# lpc1788_board.net
KiCad netlist of a schematic drawn in EAGLE
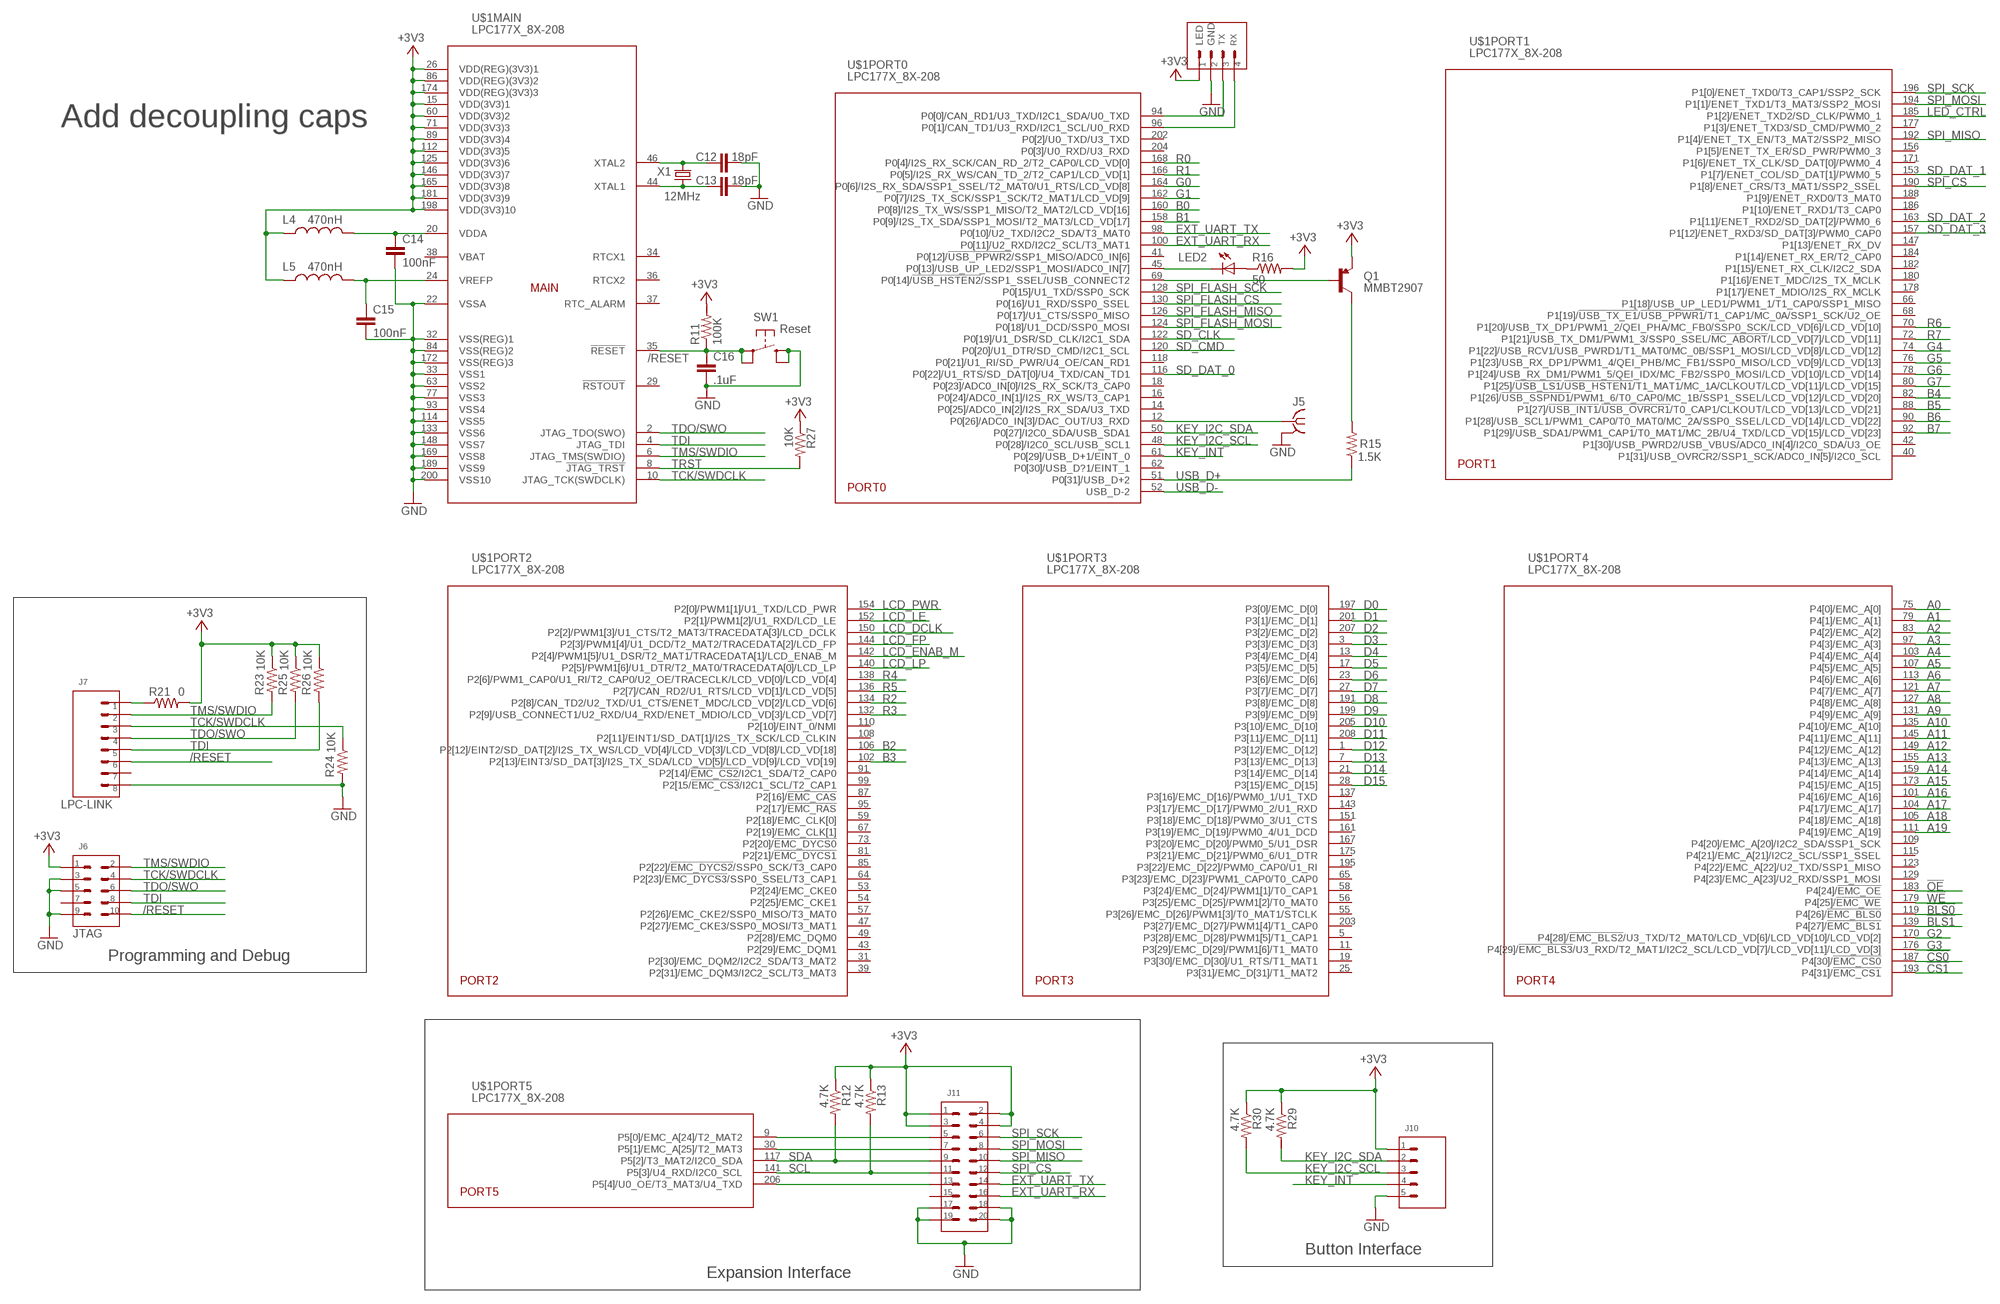
[diagram p0: schematic, sheet 1]
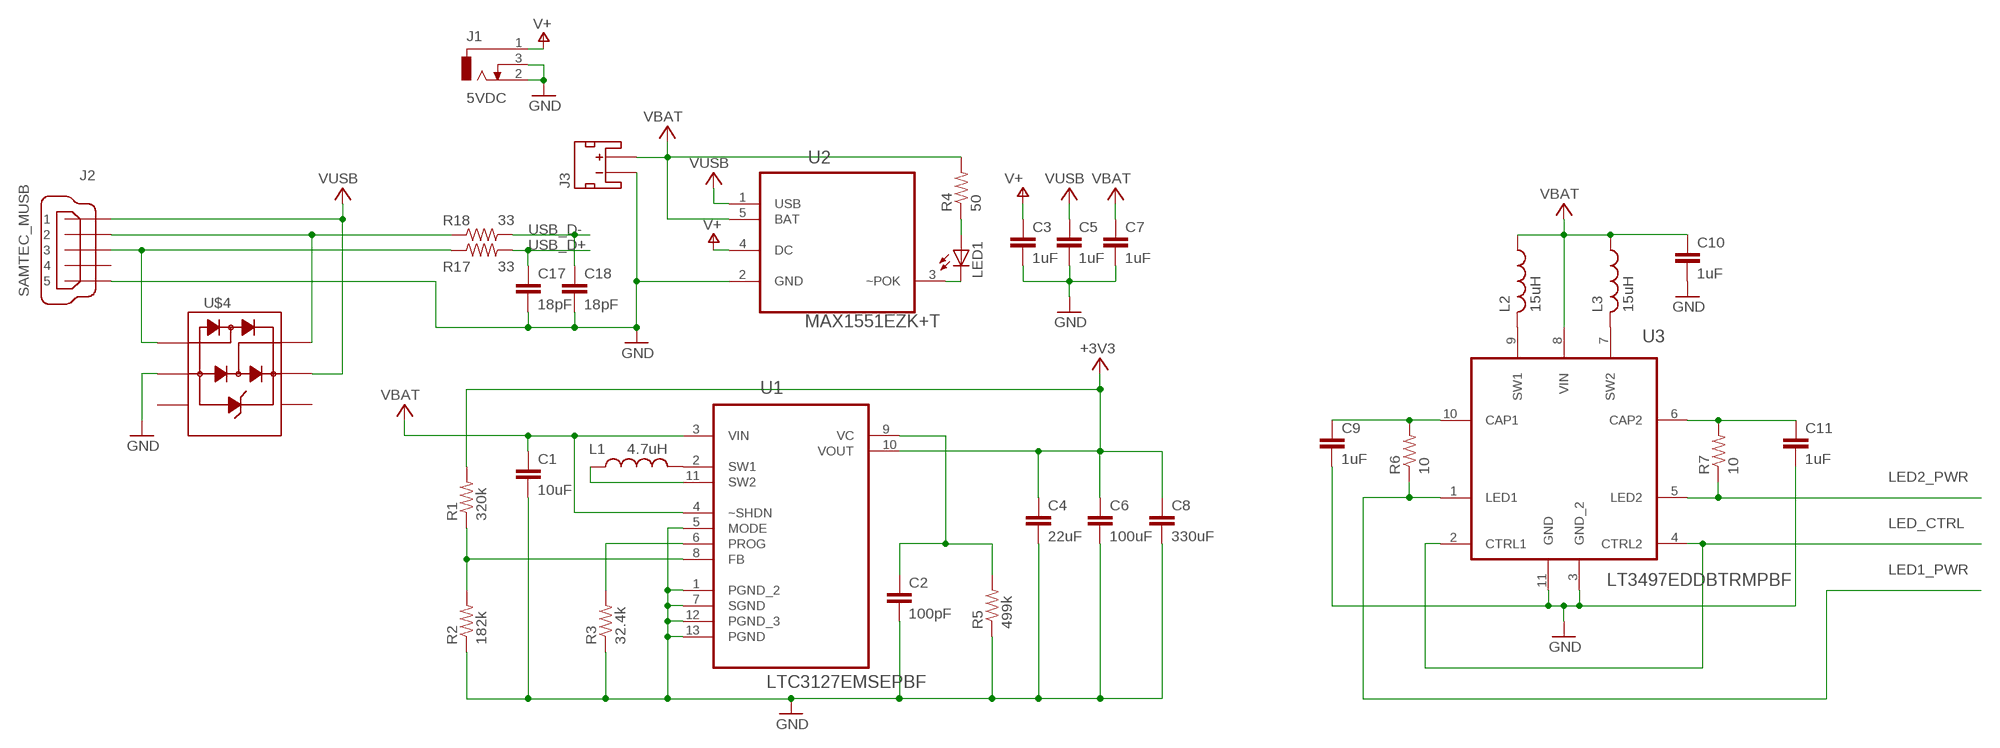
[diagram p1: schematic, sheet 2]
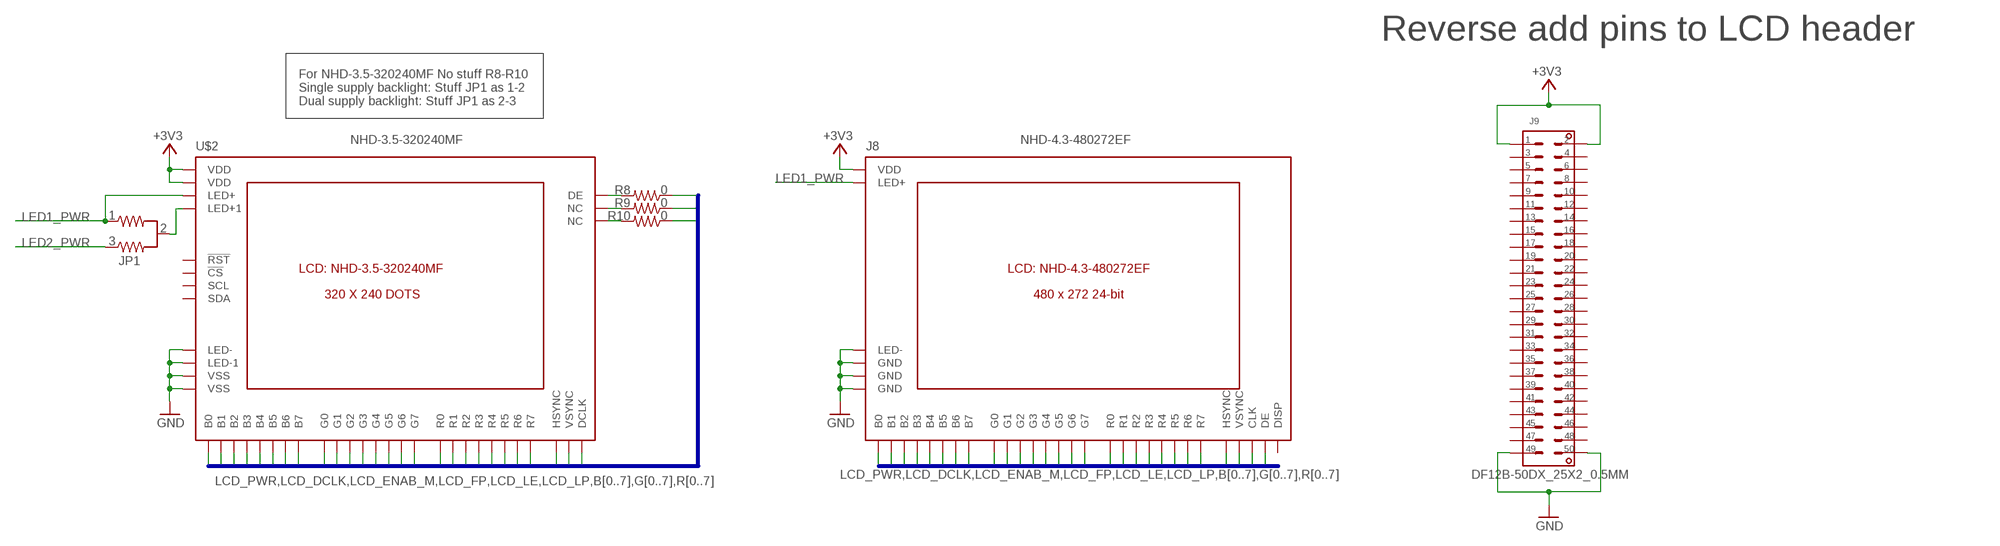
[diagram p2: schematic, sheet 3]
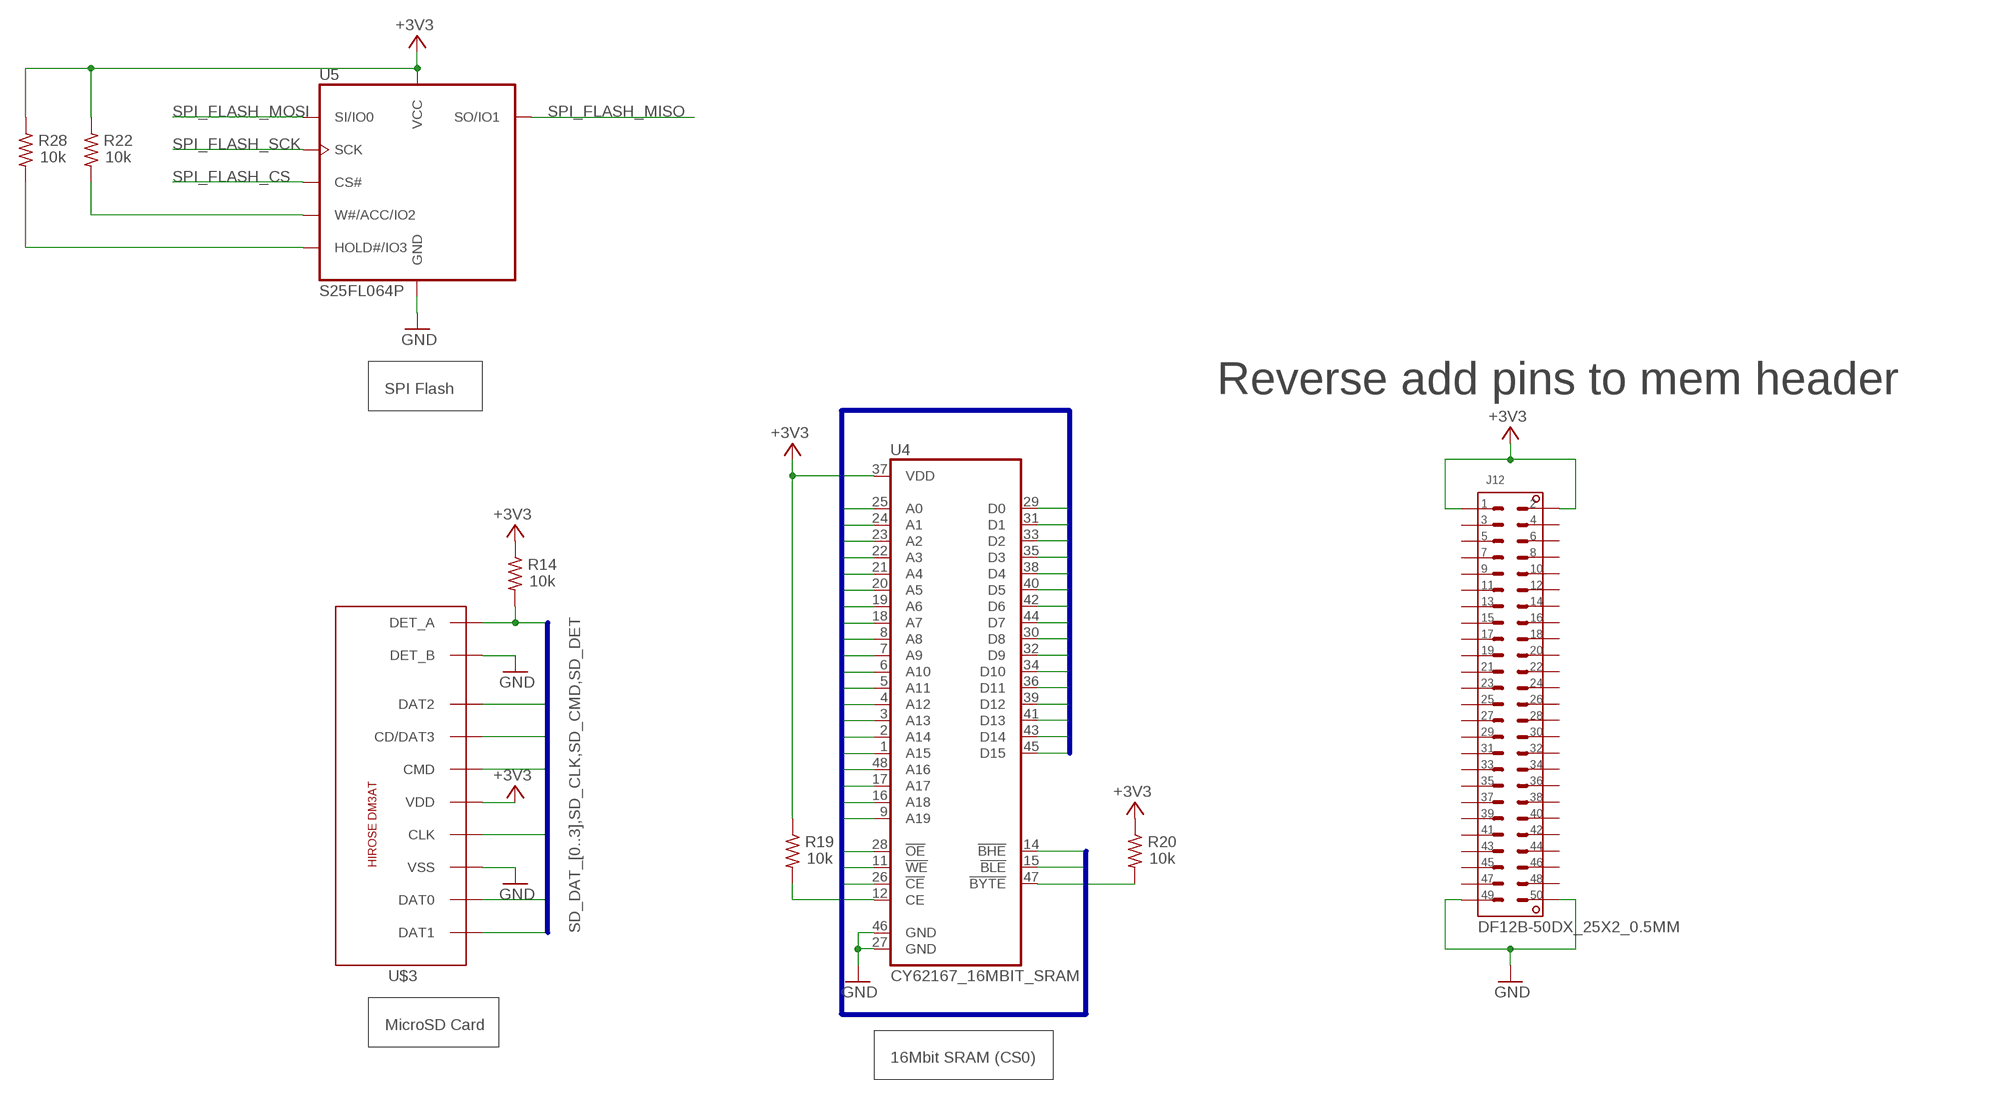
[diagram p3: schematic, sheet 4]

(export (version "E")
  (design (tool "Eeschema 10.0.6"))
  (components
    (comp (ref "C1")
      (value "10uF")
      (footprint "eagle-import:C0402")
      (libsource (lib "eagle-import") (part "C-EUC0402"))
    )
    (comp (ref "C2")
      (value "100pF")
      (footprint "eagle-import:C0402")
      (libsource (lib "eagle-import") (part "C-EUC0402"))
    )
    (comp (ref "C3")
      (value "1uF")
      (footprint "eagle-import:C0402")
      (libsource (lib "eagle-import") (part "C-EUC0402"))
    )
    (comp (ref "C4")
      (value "22uF")
      (footprint "eagle-import:C0805")
      (libsource (lib "eagle-import") (part "C-EUC0805"))
    )
    (comp (ref "C5")
      (value "1uF")
      (footprint "eagle-import:C0402")
      (libsource (lib "eagle-import") (part "C-EUC0402"))
    )
    (comp (ref "C6")
      (value "100uF")
      (footprint "eagle-import:C1206")
      (libsource (lib "eagle-import") (part "C-EUC1206"))
    )
    (comp (ref "C7")
      (value "1uF")
      (footprint "eagle-import:C0402")
      (libsource (lib "eagle-import") (part "C-EUC0402"))
    )
    (comp (ref "C8")
      (value "330uF")
      (footprint "eagle-import:C1206")
      (libsource (lib "eagle-import") (part "C-EUC1206"))
    )
    (comp (ref "C9")
      (value "1uF")
      (footprint "eagle-import:C0805")
      (libsource (lib "eagle-import") (part "C-EUC0805"))
    )
    (comp (ref "C10")
      (value "1uF")
      (footprint "eagle-import:C0402")
      (libsource (lib "eagle-import") (part "C-EUC0402"))
    )
    (comp (ref "C11")
      (value "1uF")
      (footprint "eagle-import:C0805")
      (libsource (lib "eagle-import") (part "C-EUC0805"))
    )
    (comp (ref "C17")
      (value "18pF")
      (footprint "eagle-import:C0402")
      (libsource (lib "eagle-import") (part "C-EUC0402"))
    )
    (comp (ref "C18")
      (value "18pF")
      (footprint "eagle-import:C0402")
      (libsource (lib "eagle-import") (part "C-EUC0402"))
    )
    (comp (ref "J1")
      (value "5VDC")
      (footprint "eagle-import:PJ-045")
      (libsource (lib "eagle-import") (part "DC_POWER_JACK_PJ-045"))
    )
    (comp (ref "J2")
      (value "SAMTEC_MUSB")
      (footprint "eagle-import:MUSB-05-X-B-SM-A")
      (libsource (lib "eagle-import") (part "SAMTEC_MUSB"))
    )
    (comp (ref "J3")
      (value "JST_2MM_SMT")
      (footprint "eagle-import:JST_2MM_SMT")
      (libsource (lib "eagle-import") (part "JST_2MM_SMT"))
    )
    (comp (ref "L1")
      (value "4.7uH")
      (footprint "eagle-import:NR6028")
      (libsource (lib "eagle-import") (part "INDUCTOR_NR6028"))
    )
    (comp (ref "L2")
      (value "15uH")
      (footprint "eagle-import:L3225M")
      (libsource (lib "eagle-import") (part "L-USL3225M"))
    )
    (comp (ref "L3")
      (value "15uH")
      (footprint "eagle-import:L3225M")
      (libsource (lib "eagle-import") (part "L-USL3225M"))
    )
    (comp (ref "LED1")
      (value "CHG")
      (footprint "eagle-import:CHIPLED_0603")
      (libsource (lib "eagle-import") (part "LEDCHIPLED_0603"))
    )
    (comp (ref "R1")
      (value "320k")
      (footprint "eagle-import:R0402")
      (libsource (lib "eagle-import") (part "R-US_R0402"))
    )
    (comp (ref "R2")
      (value "182k")
      (footprint "eagle-import:R0402")
      (libsource (lib "eagle-import") (part "R-US_R0402"))
    )
    (comp (ref "R3")
      (value "32.4k")
      (footprint "eagle-import:R0402")
      (libsource (lib "eagle-import") (part "R-US_R0402"))
    )
    (comp (ref "R4")
      (value "50")
      (footprint "eagle-import:R0402")
      (libsource (lib "eagle-import") (part "R-US_R0402"))
    )
    (comp (ref "R5")
      (value "499k")
      (footprint "eagle-import:R0402")
      (libsource (lib "eagle-import") (part "R-US_R0402"))
    )
    (comp (ref "R6")
      (value "10")
      (footprint "eagle-import:R0402")
      (libsource (lib "eagle-import") (part "R-US_R0402"))
    )
    (comp (ref "R7")
      (value "10")
      (footprint "eagle-import:R0402")
      (libsource (lib "eagle-import") (part "R-US_R0402"))
    )
    (comp (ref "R17")
      (value "33")
      (footprint "eagle-import:R0402")
      (libsource (lib "eagle-import") (part "R-US_R0402"))
    )
    (comp (ref "R18")
      (value "33")
      (footprint "eagle-import:R0402")
      (libsource (lib "eagle-import") (part "R-US_R0402"))
    )
    (comp (ref "U$4")
      (value "NUP2202")
      (footprint "eagle-import:SC-88")
      (libsource (lib "eagle-import") (part "NUP2202"))
    )
    (comp (ref "U1")
      (value "LTC3127EMSEPBF")
      (footprint "eagle-import:SOP65P490X110-13N")
      (fields (field (name "MANUFACTURER") "LTC3127EMSE#PBF"))
      (libsource (lib "eagle-import") (part "LTC3127EMSEPBF"))
    )
    (comp (ref "U2")
      (value "MAX1551EZK+T")
      (footprint "eagle-import:SOT95P275X110-5N")
      (libsource (lib "eagle-import") (part "MAX1551EZK+T"))
    )
    (comp (ref "U3")
      (value "LT3497EDDBTRMPBF")
      (footprint "eagle-import:DFN300X200X80-11N")
      (fields (field (name "MPN") "LT3497EDDB#TRMPBF"))
      (libsource (lib "eagle-import") (part "LT3497EDDBTRMPBF"))
    )
    (comp (ref "C12")
      (value "18pF")
      (footprint "eagle-import:C0603")
      (libsource (lib "eagle-import") (part "C-EUC0603"))
    )
    (comp (ref "C13")
      (value "18pF")
      (footprint "eagle-import:C0603")
      (libsource (lib "eagle-import") (part "C-EUC0603"))
    )
    (comp (ref "C14")
      (value "100nF")
      (footprint "eagle-import:C0402")
      (libsource (lib "eagle-import") (part "C-EUC0402"))
    )
    (comp (ref "C15")
      (value "100nF")
      (footprint "eagle-import:C0402")
      (libsource (lib "eagle-import") (part "C-EUC0402"))
    )
    (comp (ref "C16")
      (value ".1uF")
      (footprint "eagle-import:C0603")
      (libsource (lib "eagle-import") (part "C-EUC0603"))
    )
    (comp (ref "J4")
      (value "Console")
      (footprint "eagle-import:4-PIN_1.25MM")
      (libsource (lib "eagle-import") (part "FLEX_SERIAL_HEADER"))
    )
    (comp (ref "J5")
      (value "SMA-J-P-X-ST-EM1")
      (footprint "eagle-import:SMA-J-P-X-ST-EM1")
      (libsource (lib "eagle-import") (part "SMA-J-P-X-ST-EM1"))
    )
    (comp (ref "J6")
      (value "JTAG")
      (footprint "eagle-import:10-PIN_5X2_.050IN_SMT")
      (libsource (lib "eagle-import") (part "10PIN_5X2_.050IN"))
    )
    (comp (ref "J7")
      (value "JTAG")
      (footprint "eagle-import:8-PIN_SIP_.100IN")
      (libsource (lib "eagle-import") (part "8PIN_SIP_.100IN"))
    )
    (comp (ref "J10")
      (value "MOLEX_527930570_5PIN_FFC_CONNECTOR")
      (footprint "eagle-import:MOLEX_527930570")
      (libsource (lib "eagle-import") (part "MOLEX_527930570_5PIN_FFC_CONNECTOR"))
    )
    (comp (ref "J11")
      (value "20PIN_10X2_.100IN")
      (footprint "eagle-import:20-PIN_10X2_.100IN")
      (libsource (lib "eagle-import") (part "20PIN_10X2_.100IN"))
    )
    (comp (ref "L4")
      (value "470nH")
      (footprint "eagle-import:0603")
      (libsource (lib "eagle-import") (part "INDUCTOR_0603"))
    )
    (comp (ref "L5")
      (value "470nH")
      (footprint "eagle-import:0603")
      (libsource (lib "eagle-import") (part "INDUCTOR_0603"))
    )
    (comp (ref "LED2")
      (value "CHG")
      (footprint "eagle-import:CHIPLED_0603")
      (libsource (lib "eagle-import") (part "LEDCHIPLED_0603"))
    )
    (comp (ref "Q1")
      (value "MMBT2907")
      (footprint "eagle-import:SOT23")
      (libsource (lib "eagle-import") (part "TRANSISTOR_PNPMMBT4403"))
    )
    (comp (ref "R11")
      (value "100K")
      (footprint "eagle-import:R0603")
      (libsource (lib "eagle-import") (part "R-US_R0603"))
    )
    (comp (ref "R12")
      (value "4.7K")
      (footprint "eagle-import:R0603")
      (libsource (lib "eagle-import") (part "R-US_R0603"))
    )
    (comp (ref "R13")
      (value "4.7K")
      (footprint "eagle-import:R0603")
      (libsource (lib "eagle-import") (part "R-US_R0603"))
    )
    (comp (ref "R15")
      (value "1.5K")
      (footprint "eagle-import:R0603")
      (libsource (lib "eagle-import") (part "R-US_R0603"))
    )
    (comp (ref "R16")
      (value "50")
      (footprint "eagle-import:R0402")
      (libsource (lib "eagle-import") (part "R-US_R0402"))
    )
    (comp (ref "R21")
      (value "0")
      (footprint "eagle-import:R0603")
      (libsource (lib "eagle-import") (part "R-US_R0603"))
    )
    (comp (ref "R23")
      (value "10K")
      (footprint "eagle-import:R0603")
      (libsource (lib "eagle-import") (part "R-US_R0603"))
    )
    (comp (ref "R24")
      (value "10K")
      (footprint "eagle-import:R0603")
      (libsource (lib "eagle-import") (part "R-US_R0603"))
    )
    (comp (ref "R25")
      (value "10K")
      (footprint "eagle-import:R0603")
      (libsource (lib "eagle-import") (part "R-US_R0603"))
    )
    (comp (ref "R26")
      (value "10K")
      (footprint "eagle-import:R0603")
      (libsource (lib "eagle-import") (part "R-US_R0603"))
    )
    (comp (ref "R27")
      (value "10K")
      (footprint "eagle-import:R0603")
      (libsource (lib "eagle-import") (part "R-US_R0603"))
    )
    (comp (ref "R29")
      (value "4.7K")
      (footprint "eagle-import:R0603")
      (libsource (lib "eagle-import") (part "R-US_R0603"))
    )
    (comp (ref "R30")
      (value "4.7K")
      (footprint "eagle-import:R0603")
      (libsource (lib "eagle-import") (part "R-US_R0603"))
    )
    (comp (ref "SW1")
      (value "Reset")
      (footprint "eagle-import:SMT_PUSHBUTTON")
      (libsource (lib "eagle-import") (part "SMT_PUSHBUTTON"))
    )
    (comp (ref "U$1")
      (value "LPC177X_8X-208")
      (footprint "eagle-import:LQFP208")
      (libsource (lib "eagle-import") (part "LPC177X_8X-208"))
    )
    (comp (ref "X1")
      (value "12MHz")
      (footprint "eagle-import:2-SMD_8MMX4.5MM")
      (libsource (lib "eagle-import") (part "XTAL_2SMD_8MMX4.5MM12MHZ"))
    )
    (comp (ref "J12")
      (value "DF12B-50DX_25X2_0.5MM")
      (footprint "eagle-import:DF12B-50DX_25X2_0.5MM")
      (libsource (lib "eagle-import") (part "DF12B-50DX_25X2_0.5MM"))
    )
    (comp (ref "R14")
      (value "10k")
      (footprint "eagle-import:R0402")
      (libsource (lib "eagle-import") (part "R-US_R0402"))
    )
    (comp (ref "R19")
      (value "10k")
      (footprint "eagle-import:R0402")
      (libsource (lib "eagle-import") (part "R-US_R0402"))
    )
    (comp (ref "R20")
      (value "10k")
      (footprint "eagle-import:R0402")
      (libsource (lib "eagle-import") (part "R-US_R0402"))
    )
    (comp (ref "R22")
      (value "10k")
      (footprint "eagle-import:R0402")
      (libsource (lib "eagle-import") (part "R-US_R0402"))
    )
    (comp (ref "R28")
      (value "10k")
      (footprint "eagle-import:R0402")
      (libsource (lib "eagle-import") (part "R-US_R0402"))
    )
    (comp (ref "U$3")
      (value "DM3AT")
      (footprint "eagle-import:DM3AT")
      (libsource (lib "eagle-import") (part "DM3AT"))
    )
    (comp (ref "U4")
      (value "CY62167_16MBIT_SRAM")
      (footprint "eagle-import:TSOP48")
      (libsource (lib "eagle-import") (part "CY62167_16MBIT_SRAM"))
    )
    (comp (ref "U5")
      (value "S25FL064P")
      (footprint "eagle-import:SO3_016")
      (libsource (lib "eagle-import") (part "S25FL064P"))
    )
    (comp (ref "J8")
      (value "NHD-4.3-480272EF")
      (footprint "eagle-import:FCI_62684-402100ALF")
      (libsource (lib "eagle-import") (part "NHD-4.3-480272EF"))
    )
    (comp (ref "J9")
      (value "DF12B-50DX_25X2_0.5MM")
      (footprint "eagle-import:DF12B-50DX_25X2_0.5MM")
      (libsource (lib "eagle-import") (part "DF12B-50DX_25X2_0.5MM"))
    )
    (comp (ref "JP1")
      (value "RESISTOR_JUMPER_0402")
      (footprint "eagle-import:RESISTOR_JUMPER_0402")
      (libsource (lib "eagle-import") (part "RESISTOR_JUMPER_0402"))
    )
    (comp (ref "R8")
      (value "0")
      (footprint "eagle-import:R0402")
      (libsource (lib "eagle-import") (part "R-US_R0402"))
    )
    (comp (ref "R9")
      (value "0")
      (footprint "eagle-import:R0402")
      (libsource (lib "eagle-import") (part "R-US_R0402"))
    )
    (comp (ref "R10")
      (value "0")
      (footprint "eagle-import:R0402")
      (libsource (lib "eagle-import") (part "R-US_R0402"))
    )
    (comp (ref "U$2")
      (value "NHD-3.5-320240MF")
      (footprint "eagle-import:MOLEX_51296-5494")
      (libsource (lib "eagle-import") (part "NHD-3.5-320240MF"))
    )
  )
  (nets
    (net (code "2") (name "+3V3") (class "Default")
      (node (ref "C4") (pin "1") (pinfunction "1_1") (pintype "passive"))
      (node (ref "C6") (pin "1") (pinfunction "1_1") (pintype "passive"))
      (node (ref "C8") (pin "1") (pinfunction "1_1") (pintype "passive"))
      (node (ref "J10") (pin "P$1") (pinfunction "S1_P$1") (pintype "passive"))
      (node (ref "J11") (pin "1") (pinfunction "S1_1") (pintype "passive"))
      (node (ref "J11") (pin "2") (pinfunction "S2_2") (pintype "passive"))
      (node (ref "J11") (pin "3") (pinfunction "S3_3") (pintype "passive"))
      (node (ref "J11") (pin "4") (pinfunction "S4_4") (pintype "passive"))
      (node (ref "J12") (pin "P$1") (pinfunction "S1_P$1") (pintype "passive"))
      (node (ref "J12") (pin "P$2") (pinfunction "S2_P$2") (pintype "passive"))
      (node (ref "J4") (pin "1") (pinfunction "S1_1") (pintype "passive"))
      (node (ref "J6") (pin "P$1") (pinfunction "S1_P$1") (pintype "passive"))
      (node (ref "J8") (pin "P$4") (pinfunction "VDD_P$4") (pintype "power_in"))
      (node (ref "J9") (pin "P$1") (pinfunction "S1_P$1") (pintype "passive"))
      (node (ref "J9") (pin "P$2") (pinfunction "S2_P$2") (pintype "passive"))
      (node (ref "L4") (pin "1") (pinfunction "1_1") (pintype "passive"))
      (node (ref "L5") (pin "1") (pinfunction "1_1") (pintype "passive"))
      (node (ref "Q1") (pin "2") (pinfunction "E_2") (pintype "passive"))
      (node (ref "R1") (pin "2") (pinfunction "2_2") (pintype "passive"))
      (node (ref "R11") (pin "2") (pinfunction "2_2") (pintype "passive"))
      (node (ref "R12") (pin "1") (pinfunction "1_1") (pintype "passive"))
      (node (ref "R13") (pin "1") (pinfunction "1_1") (pintype "passive"))
      (node (ref "R14") (pin "1") (pinfunction "1_1") (pintype "passive"))
      (node (ref "R16") (pin "2") (pinfunction "2_2") (pintype "passive"))
      (node (ref "R19") (pin "1") (pinfunction "1_1") (pintype "passive"))
      (node (ref "R20") (pin "1") (pinfunction "1_1") (pintype "passive"))
      (node (ref "R21") (pin "2") (pinfunction "2_2") (pintype "passive"))
      (node (ref "R22") (pin "1") (pinfunction "1_1") (pintype "passive"))
      (node (ref "R23") (pin "1") (pinfunction "1_1") (pintype "passive"))
      (node (ref "R25") (pin "1") (pinfunction "1_1") (pintype "passive"))
      (node (ref "R26") (pin "1") (pinfunction "1_1") (pintype "passive"))
      (node (ref "R27") (pin "1") (pinfunction "1_1") (pintype "passive"))
      (node (ref "R28") (pin "1") (pinfunction "1_1") (pintype "passive"))
      (node (ref "R29") (pin "1") (pinfunction "1_1") (pintype "passive"))
      (node (ref "R30") (pin "1") (pinfunction "1_1") (pintype "passive"))
      (node (ref "U$1") (pin "112") (pinfunction "VDD(3V3)5_112") (pintype "bidirectional"))
      (node (ref "U$1") (pin "125") (pinfunction "VDD(3V3)6_125") (pintype "bidirectional"))
      (node (ref "U$1") (pin "146") (pinfunction "VDD(3V3)7_146") (pintype "bidirectional"))
      (node (ref "U$1") (pin "15") (pinfunction "VDD(3V3)1_15") (pintype "bidirectional"))
      (node (ref "U$1") (pin "165") (pinfunction "VDD(3V3)8_165") (pintype "bidirectional"))
      (node (ref "U$1") (pin "174") (pinfunction "VDD(REG)(3V3)3_174") (pintype "bidirectional"))
      (node (ref "U$1") (pin "181") (pinfunction "VDD(3V3)9_181") (pintype "bidirectional"))
      (node (ref "U$1") (pin "198") (pinfunction "VDD(3V3)10_198") (pintype "bidirectional"))
      (node (ref "U$1") (pin "26") (pinfunction "VDD(REG)(3V3)1_26") (pintype "bidirectional"))
      (node (ref "U$1") (pin "60") (pinfunction "VDD(3V3)2_60") (pintype "bidirectional"))
      (node (ref "U$1") (pin "71") (pinfunction "VDD(3V3)3_71") (pintype "bidirectional"))
      (node (ref "U$1") (pin "86") (pinfunction "VDD(REG)(3V3)2_86") (pintype "bidirectional"))
      (node (ref "U$1") (pin "89") (pinfunction "VDD(3V3)4_89") (pintype "bidirectional"))
      (node (ref "U$2") (pin "P$41") (pinfunction "VDD_P$41") (pintype "power_in"))
      (node (ref "U$2") (pin "P$42") (pinfunction "VDD_P$42") (pintype "power_in"))
      (node (ref "U$3") (pin "VDD") (pinfunction "VDD_VDD") (pintype "bidirectional"))
      (node (ref "U1") (pin "10") (pinfunction "VOUT_10") (pintype "bidirectional"))
      (node (ref "U4") (pin "37") (pinfunction "VDD_37") (pintype "power_in"))
      (node (ref "U5") (pin "P$2") (pinfunction "VCC_P$2") (pintype "power_in"))
    )
    (net (code "3") (name "+VBAT") (class "Default")
      (node (ref "C1") (pin "1") (pinfunction "1_1") (pintype "passive"))
      (node (ref "C10") (pin "1") (pinfunction "1_1") (pintype "passive"))
      (node (ref "C7") (pin "1") (pinfunction "1_1") (pintype "passive"))
      (node (ref "J3") (pin "2") (pinfunction "+_2") (pintype "bidirectional"))
      (node (ref "L2") (pin "1") (pinfunction "1_1") (pintype "passive"))
      (node (ref "L3") (pin "1") (pinfunction "1_1") (pintype "passive"))
      (node (ref "R4") (pin "2") (pinfunction "2_2") (pintype "passive"))
      (node (ref "U1") (pin "3") (pinfunction "VIN_3") (pintype "power_in"))
      (node (ref "U1") (pin "4") (pinfunction "~{SHDN}_4") (pintype "input"))
      (node (ref "U2") (pin "5") (pinfunction "BAT_5") (pintype "power_in"))
      (node (ref "U3") (pin "8") (pinfunction "VIN_8") (pintype "power_in"))
    )
    (net (code "4") (name "+VUSB") (class "Default")
      (node (ref "C5") (pin "1") (pinfunction "1_1") (pintype "passive"))
      (node (ref "J2") (pin "1") (pinfunction "1_1") (pintype "power_in"))
      (node (ref "U$4") (pin "P$5") (pinfunction "P$5_P$5") (pintype "power_in"))
      (node (ref "U2") (pin "1") (pinfunction "USB_1") (pintype "power_in"))
    )
    (net (code "7") (name "A0") (class "Default")
      (node (ref "U$1") (pin "75") (pinfunction "P4[0]/EMC_A[0]_75") (pintype "bidirectional"))
      (node (ref "U4") (pin "25") (pinfunction "A0_25") (pintype "input"))
    )
    (net (code "8") (name "A1") (class "Default")
      (node (ref "U$1") (pin "79") (pinfunction "P4[1]/EMC_A[1]_79") (pintype "bidirectional"))
      (node (ref "U4") (pin "24") (pinfunction "A1_24") (pintype "input"))
    )
    (net (code "9") (name "A2") (class "Default")
      (node (ref "U$1") (pin "83") (pinfunction "P4[2]/EMC_A[2]_83") (pintype "bidirectional"))
      (node (ref "U4") (pin "23") (pinfunction "A2_23") (pintype "input"))
    )
    (net (code "10") (name "A3") (class "Default")
      (node (ref "U$1") (pin "97") (pinfunction "P4[3]/EMC_A[3]_97") (pintype "bidirectional"))
      (node (ref "U4") (pin "22") (pinfunction "A3_22") (pintype "input"))
    )
    (net (code "11") (name "A4") (class "Default")
      (node (ref "U$1") (pin "103") (pinfunction "P4[4]/EMC_A[4]_103") (pintype "bidirectional"))
      (node (ref "U4") (pin "21") (pinfunction "A4_21") (pintype "input"))
    )
    (net (code "12") (name "A5") (class "Default")
      (node (ref "U$1") (pin "107") (pinfunction "P4[5]/EMC_A[5]_107") (pintype "bidirectional"))
      (node (ref "U4") (pin "20") (pinfunction "A5_20") (pintype "input"))
    )
    (net (code "13") (name "A6") (class "Default")
      (node (ref "U$1") (pin "113") (pinfunction "P4[6]/EMC_A[6]_113") (pintype "bidirectional"))
      (node (ref "U4") (pin "19") (pinfunction "A6_19") (pintype "input"))
    )
    (net (code "14") (name "A7") (class "Default")
      (node (ref "U$1") (pin "121") (pinfunction "P4[7]/EMC_A[7]_121") (pintype "bidirectional"))
      (node (ref "U4") (pin "18") (pinfunction "A7_18") (pintype "input"))
    )
    (net (code "15") (name "A8") (class "Default")
      (node (ref "U$1") (pin "127") (pinfunction "P4[8]/EMC_A[8]_127") (pintype "bidirectional"))
      (node (ref "U4") (pin "8") (pinfunction "A8_8") (pintype "input"))
    )
    (net (code "16") (name "A9") (class "Default")
      (node (ref "U$1") (pin "131") (pinfunction "P4[9]/EMC_A[9]_131") (pintype "bidirectional"))
      (node (ref "U4") (pin "7") (pinfunction "A9_7") (pintype "input"))
    )
    (net (code "17") (name "A10") (class "Default")
      (node (ref "U$1") (pin "135") (pinfunction "P4[10]/EMC_A[10]_135") (pintype "bidirectional"))
      (node (ref "U4") (pin "6") (pinfunction "A10_6") (pintype "input"))
    )
    (net (code "18") (name "A11") (class "Default")
      (node (ref "U$1") (pin "145") (pinfunction "P4[11]/EMC_A[11]_145") (pintype "bidirectional"))
      (node (ref "U4") (pin "5") (pinfunction "A11_5") (pintype "input"))
    )
    (net (code "19") (name "A12") (class "Default")
      (node (ref "U$1") (pin "149") (pinfunction "P4[12]/EMC_A[12]_149") (pintype "bidirectional"))
      (node (ref "U4") (pin "4") (pinfunction "A12_4") (pintype "input"))
    )
    (net (code "20") (name "A13") (class "Default")
      (node (ref "U$1") (pin "155") (pinfunction "P4[13]/EMC_A[13]_155") (pintype "bidirectional"))
      (node (ref "U4") (pin "3") (pinfunction "A13_3") (pintype "input"))
    )
    (net (code "21") (name "A14") (class "Default")
      (node (ref "U$1") (pin "159") (pinfunction "P4[14]/EMC_A[14]_159") (pintype "bidirectional"))
      (node (ref "U4") (pin "2") (pinfunction "A14_2") (pintype "input"))
    )
    (net (code "22") (name "A15") (class "Default")
      (node (ref "U$1") (pin "173") (pinfunction "P4[15]/EMC_A[15]_173") (pintype "bidirectional"))
      (node (ref "U4") (pin "1") (pinfunction "A15_1") (pintype "input"))
    )
    (net (code "23") (name "A16") (class "Default")
      (node (ref "U$1") (pin "101") (pinfunction "P4[16]/EMC_A[16]_101") (pintype "bidirectional"))
      (node (ref "U4") (pin "48") (pinfunction "A16_48") (pintype "input"))
    )
    (net (code "24") (name "A17") (class "Default")
      (node (ref "U$1") (pin "104") (pinfunction "P4[17]/EMC_A[17]_104") (pintype "bidirectional"))
      (node (ref "U4") (pin "17") (pinfunction "A17_17") (pintype "input"))
    )
    (net (code "25") (name "A18") (class "Default")
      (node (ref "U$1") (pin "105") (pinfunction "P4[18]/EMC_A[18]_105") (pintype "bidirectional"))
      (node (ref "U4") (pin "16") (pinfunction "A18_16") (pintype "input"))
    )
    (net (code "26") (name "A19") (class "Default")
      (node (ref "U$1") (pin "111") (pinfunction "P4[19]/EMC_A[19]_111") (pintype "bidirectional"))
      (node (ref "U4") (pin "9") (pinfunction "A19_9") (pintype "input"))
    )
    (net (code "27") (name "B0") (class "Default")
      (node (ref "J8") (pin "P$21") (pinfunction "B0_P$21") (pintype "bidirectional"))
      (node (ref "U$1") (pin "160") (pinfunction "P0[8]/I2S_TX_WS/SSP1_MISO/T2_MAT2/LCD_VD[16]_160") (pintype "bidirectional"))
      (node (ref "U$2") (pin "P$12") (pinfunction "B0_P$12") (pintype "bidirectional"))
    )
    (net (code "28") (name "B1") (class "Default")
      (node (ref "J8") (pin "P$22") (pinfunction "B1_P$22") (pintype "bidirectional"))
      (node (ref "U$1") (pin "158") (pinfunction "P0[9]/I2S_TX_SDA/SSP1_MOSI/T2_MAT3/LCD_VD[17]_158") (pintype "bidirectional"))
      (node (ref "U$2") (pin "P$13") (pinfunction "B1_P$13") (pintype "bidirectional"))
    )
    (net (code "29") (name "B2") (class "Default")
      (node (ref "J8") (pin "P$23") (pinfunction "B2_P$23") (pintype "bidirectional"))
      (node (ref "U$1") (pin "106") (pinfunction "P2[12]/EINT2/SD_DAT[2]/I2S_TX_WS/LCD_VD[4]/LCD_VD[3]/LCD_VD[8]/LCD_VD[18]_106") (pintype "bidirectional"))
      (node (ref "U$2") (pin "P$14") (pinfunction "B2_P$14") (pintype "bidirectional"))
    )
    (net (code "30") (name "B3") (class "Default")
      (node (ref "J8") (pin "P$24") (pinfunction "B3_P$24") (pintype "bidirectional"))
      (node (ref "U$1") (pin "102") (pinfunction "P2[13]/EINT3/SD_DAT[3]/I2S_TX_SDA/LCD_VD[5]/LCD_VD[9]/LCD_VD[19]_102") (pintype "bidirectional"))
      (node (ref "U$2") (pin "P$15") (pinfunction "B3_P$15") (pintype "bidirectional"))
    )
    (net (code "31") (name "B4") (class "Default")
      (node (ref "J8") (pin "P$25") (pinfunction "B4_P$25") (pintype "bidirectional"))
      (node (ref "U$1") (pin "82") (pinfunction "P1[26]/~{USB_SSPND1}/PWM1_6/T0_CAP0/MC_1B/SSP1_SSEL/LCD_VD[12]/LCD_VD[20]_82") (pintype "bidirectional"))
      (node (ref "U$2") (pin "P$16") (pinfunction "B4_P$16") (pintype "bidirectional"))
    )
    (net (code "32") (name "B5") (class "Default")
      (node (ref "J8") (pin "P$26") (pinfunction "B5_P$26") (pintype "bidirectional"))
      (node (ref "U$1") (pin "88") (pinfunction "P1[27]/~{USB_INT1}/~{USB_OVRCR1}/T0_CAP1/CLKOUT/LCD_VD[13]/LCD_VD[21]_88") (pintype "bidirectional"))
      (node (ref "U$2") (pin "P$17") (pinfunction "B5_P$17") (pintype "bidirectional"))
    )
    (net (code "33") (name "B6") (class "Default")
      (node (ref "J8") (pin "P$27") (pinfunction "B6_P$27") (pintype "bidirectional"))
      (node (ref "U$1") (pin "90") (pinfunction "P1[28]/USB_SCL1/PWM1_CAP0/T0_MAT0/MC_2A/SSP0_SSEL/LCD_VD[14]/LCD_VD[22]_90") (pintype "bidirectional"))
      (node (ref "U$2") (pin "P$18") (pinfunction "B6_P$18") (pintype "bidirectional"))
    )
    (net (code "34") (name "B7") (class "Default")
      (node (ref "J8") (pin "P$28") (pinfunction "B7_P$28") (pintype "bidirectional"))
      (node (ref "U$1") (pin "92") (pinfunction "P1[29]/USB_SDA1/PWM1_CAP1/T0_MAT1/MC_2B/U4_TXD/LCD_VD[15]/LCD_VD[23]_92") (pintype "bidirectional"))
      (node (ref "U$2") (pin "P$19") (pinfunction "B7_P$19") (pintype "bidirectional"))
    )
    (net (code "35") (name "D0") (class "Default")
      (node (ref "U$1") (pin "197") (pinfunction "P3[0]/EMC_D[0]_197") (pintype "bidirectional"))
      (node (ref "U4") (pin "29") (pinfunction "D0_29") (pintype "bidirectional"))
    )
    (net (code "36") (name "D1") (class "Default")
      (node (ref "U$1") (pin "201") (pinfunction "P3[1]/EMC_D[1]_201") (pintype "bidirectional"))
      (node (ref "U4") (pin "31") (pinfunction "D1_31") (pintype "bidirectional"))
    )
    (net (code "37") (name "D2") (class "Default")
      (node (ref "U$1") (pin "207") (pinfunction "P3[2]/EMC_D[2]_207") (pintype "bidirectional"))
      (node (ref "U4") (pin "33") (pinfunction "D2_33") (pintype "bidirectional"))
    )
    (net (code "38") (name "D3") (class "Default")
      (node (ref "U$1") (pin "3") (pinfunction "P3[3]/EMC_D[3]_3") (pintype "bidirectional"))
      (node (ref "U4") (pin "35") (pinfunction "D3_35") (pintype "bidirectional"))
    )
    (net (code "39") (name "D4") (class "Default")
      (node (ref "U$1") (pin "13") (pinfunction "P3[4]/EMC_D[4]_13") (pintype "bidirectional"))
      (node (ref "U4") (pin "38") (pinfunction "D4_38") (pintype "bidirectional"))
    )
    (net (code "40") (name "D5") (class "Default")
      (node (ref "U$1") (pin "17") (pinfunction "P3[5]/EMC_D[5]_17") (pintype "bidirectional"))
      (node (ref "U4") (pin "40") (pinfunction "D5_40") (pintype "bidirectional"))
    )
    (net (code "41") (name "D6") (class "Default")
      (node (ref "U$1") (pin "23") (pinfunction "P3[6]/EMC_D[6]_23") (pintype "bidirectional"))
      (node (ref "U4") (pin "42") (pinfunction "D6_42") (pintype "bidirectional"))
    )
    (net (code "42") (name "D7") (class "Default")
      (node (ref "U$1") (pin "27") (pinfunction "P3[7]/EMC_D[7]_27") (pintype "bidirectional"))
      (node (ref "U4") (pin "44") (pinfunction "D7_44") (pintype "bidirectional"))
    )
    (net (code "43") (name "D8") (class "Default")
      (node (ref "U$1") (pin "191") (pinfunction "P3[8]/EMC_D[8]_191") (pintype "bidirectional"))
      (node (ref "U4") (pin "30") (pinfunction "D8_30") (pintype "bidirectional"))
    )
    (net (code "44") (name "D9") (class "Default")
      (node (ref "U$1") (pin "199") (pinfunction "P3[9]/EMC_D[9]_199") (pintype "bidirectional"))
      (node (ref "U4") (pin "32") (pinfunction "D9_32") (pintype "bidirectional"))
    )
    (net (code "45") (name "D10") (class "Default")
      (node (ref "U$1") (pin "205") (pinfunction "P3[10]/EMC_D[10]_205") (pintype "bidirectional"))
      (node (ref "U4") (pin "34") (pinfunction "D10_34") (pintype "bidirectional"))
    )
    (net (code "46") (name "D11") (class "Default")
      (node (ref "U$1") (pin "208") (pinfunction "P3[11]/EMC_D[11]_208") (pintype "bidirectional"))
      (node (ref "U4") (pin "36") (pinfunction "D11_36") (pintype "bidirectional"))
    )
    (net (code "47") (name "D12") (class "Default")
      (node (ref "U$1") (pin "1") (pinfunction "P3[12]/EMC_D[12]_1") (pintype "bidirectional"))
      (node (ref "U4") (pin "39") (pinfunction "D12_39") (pintype "bidirectional"))
    )
    (net (code "48") (name "D13") (class "Default")
      (node (ref "U$1") (pin "7") (pinfunction "P3[13]/EMC_D[13]_7") (pintype "bidirectional"))
      (node (ref "U4") (pin "41") (pinfunction "D13_41") (pintype "bidirectional"))
    )
    (net (code "49") (name "D14") (class "Default")
      (node (ref "U$1") (pin "21") (pinfunction "P3[14]/EMC_D[14]_21") (pintype "bidirectional"))
      (node (ref "U4") (pin "43") (pinfunction "D14_43") (pintype "bidirectional"))
    )
    (net (code "50") (name "D15") (class "Default")
      (node (ref "U$1") (pin "28") (pinfunction "P3[15]/EMC_D[15]_28") (pintype "bidirectional"))
      (node (ref "U4") (pin "45") (pinfunction "D15_45") (pintype "bidirectional"))
    )
    (net (code "51") (name "EXT_UART_RX") (class "Default")
      (node (ref "J11") (pin "16") (pinfunction "S16_16") (pintype "passive"))
      (node (ref "U$1") (pin "100") (pinfunction "P0[11]/U2_RXD/I2C2_SCL/T3_MAT1_100") (pintype "bidirectional"))
    )
    (net (code "52") (name "EXT_UART_TX") (class "Default")
      (node (ref "J11") (pin "14") (pinfunction "S14_14") (pintype "passive"))
      (node (ref "U$1") (pin "98") (pinfunction "P0[10]/U2_TXD/I2C2_SDA/T3_MAT0_98") (pintype "bidirectional"))
    )
    (net (code "53") (name "G0") (class "Default")
      (node (ref "J8") (pin "P$13") (pinfunction "G0_P$13") (pintype "bidirectional"))
      (node (ref "U$1") (pin "164") (pinfunction "P0[6]/I2S_RX_SDA/SSP1_SSEL/T2_MAT0/U1_RTS/LCD_VD[8]_164") (pintype "bidirectional"))
      (node (ref "U$2") (pin "P$20") (pinfunction "G0_P$20") (pintype "bidirectional"))
    )
    (net (code "54") (name "G1") (class "Default")
      (node (ref "J8") (pin "P$14") (pinfunction "G1_P$14") (pintype "bidirectional"))
      (node (ref "U$1") (pin "162") (pinfunction "P0[7]/I2S_TX_SCK/SSP1_SCK/T2_MAT1/LCD_VD[9]_162") (pintype "bidirectional"))
      (node (ref "U$2") (pin "P$21") (pinfunction "G1_P$21") (pintype "bidirectional"))
    )
    (net (code "55") (name "G2") (class "Default")
      (node (ref "J8") (pin "P$15") (pinfunction "G2_P$15") (pintype "bidirectional"))
      (node (ref "U$1") (pin "170") (pinfunction "P4[28]/~{EMC_BLS2}/U3_TXD/T2_MAT0/LCD_VD[6]/LCD_VD[10]/LCD_VD[2]_170") (pintype "bidirectional"))
      (node (ref "U$2") (pin "P$22") (pinfunction "G2_P$22") (pintype "bidirectional"))
    )
    (net (code "56") (name "G3") (class "Default")
      (node (ref "J8") (pin "P$16") (pinfunction "G3_P$16") (pintype "bidirectional"))
      (node (ref "U$1") (pin "176") (pinfunction "P4[29]/~{EMC_BLS3}/U3_RXD/T2_MAT1/I2C2_SCL/LCD_VD[7]/LCD_VD[11]/LCD_VD[3]_176") (pintype "bidirectional"))
      (node (ref "U$2") (pin "P$23") (pinfunction "G3_P$23") (pintype "bidirectional"))
    )
    (net (code "57") (name "G4") (class "Default")
      (node (ref "J8") (pin "P$17") (pinfunction "G4_P$17") (pintype "bidirectional"))
      (node (ref "U$1") (pin "74") (pinfunction "P1[22]/USB_RCV1/USB_PWRD1/T1_MAT0/MC_0B/SSP1_MOSI/LCD_VD[8]/LCD_VD[12]_74") (pintype "bidirectional"))
      (node (ref "U$2") (pin "P$24") (pinfunction "G4_P$24") (pintype "bidirectional"))
    )
    (net (code "58") (name "G5") (class "Default")
      (node (ref "J8") (pin "P$18") (pinfunction "G5_P$18") (pintype "bidirectional"))
      (node (ref "U$1") (pin "76") (pinfunction "P1[23]/USB_RX_DP1/PWM1_4/QEI_PHB/MC_FB1/SSP0_MISO/LCD_VD[9]/LCD_VD[13]_76") (pintype "bidirectional"))
      (node (ref "U$2") (pin "P$25") (pinfunction "G5_P$25") (pintype "bidirectional"))
    )
    (net (code "59") (name "G6") (class "Default")
      (node (ref "J8") (pin "P$19") (pinfunction "G6_P$19") (pintype "bidirectional"))
      (node (ref "U$1") (pin "78") (pinfunction "P1[24]/USB_RX_DM1/PWM1_5/QEI_IDX/MC_FB2/SSP0_MOSI/LCD_VD[10]/LCD_VD[14]_78") (pintype "bidirectional"))
      (node (ref "U$2") (pin "P$26") (pinfunction "G6_P$26") (pintype "bidirectional"))
    )
    (net (code "60") (name "G7") (class "Default")
      (node (ref "J8") (pin "P$20") (pinfunction "G7_P$20") (pintype "bidirectional"))
      (node (ref "U$1") (pin "80") (pinfunction "P1[25]/~{USB_LS1}/~{USB_HSTEN1}/T1_MAT1/MC_1A/CLKOUT/LCD_VD[11]/LCD_VD[15]_80") (pintype "bidirectional"))
      (node (ref "U$2") (pin "P$27") (pinfunction "G7_P$27") (pintype "bidirectional"))
    )
    (net (code "61") (name "GND") (class "Default")
      (node (ref "C1") (pin "2") (pinfunction "2_2") (pintype "passive"))
      (node (ref "C10") (pin "2") (pinfunction "2_2") (pintype "passive"))
      (node (ref "C11") (pin "2") (pinfunction "2_2") (pintype "passive"))
      (node (ref "C12") (pin "2") (pinfunction "2_2") (pintype "passive"))
      (node (ref "C13") (pin "2") (pinfunction "2_2") (pintype "passive"))
      (node (ref "C14") (pin "2") (pinfunction "2_2") (pintype "passive"))
      (node (ref "C15") (pin "2") (pinfunction "2_2") (pintype "passive"))
      (node (ref "C16") (pin "2") (pinfunction "2_2") (pintype "passive"))
      (node (ref "C17") (pin "2") (pinfunction "2_2") (pintype "passive"))
      (node (ref "C18") (pin "2") (pinfunction "2_2") (pintype "passive"))
      (node (ref "C2") (pin "2") (pinfunction "2_2") (pintype "passive"))
      (node (ref "C3") (pin "2") (pinfunction "2_2") (pintype "passive"))
      (node (ref "C4") (pin "2") (pinfunction "2_2") (pintype "passive"))
      (node (ref "C5") (pin "2") (pinfunction "2_2") (pintype "passive"))
      (node (ref "C6") (pin "2") (pinfunction "2_2") (pintype "passive"))
      (node (ref "C7") (pin "2") (pinfunction "2_2") (pintype "passive"))
      (node (ref "C8") (pin "2") (pinfunction "2_2") (pintype "passive"))
      (node (ref "C9") (pin "2") (pinfunction "2_2") (pintype "passive"))
      (node (ref "J1") (pin "2") (pinfunction "2_2") (pintype "passive"))
      (node (ref "J1") (pin "3") (pinfunction "3_3") (pintype "passive"))
      (node (ref "J10") (pin "P$5") (pinfunction "S5_P$5") (pintype "passive"))
      (node (ref "J11") (pin "17") (pinfunction "S17_17") (pintype "passive"))
      (node (ref "J11") (pin "18") (pinfunction "S18_18") (pintype "passive"))
      (node (ref "J11") (pin "19") (pinfunction "S19_19") (pintype "passive"))
      (node (ref "J11") (pin "20") (pinfunction "S20_20") (pintype "passive"))
      (node (ref "J12") (pin "P$49") (pinfunction "S49_P$49") (pintype "passive"))
      (node (ref "J12") (pin "P$50") (pinfunction "S50_P$50") (pintype "passive"))
      (node (ref "J2") (pin "5") (pinfunction "5_5") (pintype "power_in"))
      (node (ref "J3") (pin "1") (pinfunction "-_1") (pintype "bidirectional"))
      (node (ref "J4") (pin "2") (pinfunction "S2_2") (pintype "passive"))
      (node (ref "J5") (pin "G@1") (pinfunction "GND_G@1") (pintype "passive"))
      (node (ref "J6") (pin "P$3") (pinfunction "S3_P$3") (pintype "passive"))
      (node (ref "J6") (pin "P$5") (pinfunction "S5_P$5") (pintype "passive"))
      (node (ref "J6") (pin "P$9") (pinfunction "S9_P$9") (pintype "passive"))
      (node (ref "J7") (pin "8") (pinfunction "S8_8") (pintype "passive"))
      (node (ref "J8") (pin "P$1") (pinfunction "LED-_P$1") (pintype "power_in"))
      (node (ref "J8") (pin "P$29") (pinfunction "GND_P$29") (pintype "power_in"))
      (node (ref "J8") (pin "P$3") (pinfunction "GND_P$3") (pintype "power_in"))
      (node (ref "J8") (pin "P$36") (pinfunction "GND_P$36") (pintype "power_in"))
      (node (ref "J9") (pin "P$49") (pinfunction "S49_P$49") (pintype "passive"))
      (node (ref "J9") (pin "P$50") (pinfunction "S50_P$50") (pintype "passive"))
      (node (ref "R2") (pin "1") (pinfunction "1_1") (pintype "passive"))
      (node (ref "R24") (pin "2") (pinfunction "2_2") (pintype "passive"))
      (node (ref "R3") (pin "1") (pinfunction "1_1") (pintype "passive"))
      (node (ref "R5") (pin "1") (pinfunction "1_1") (pintype "passive"))
      (node (ref "SW1") (pin "P$3") (pinfunction "S1_P$3") (pintype "passive"))
      (node (ref "SW1") (pin "P$4") (pinfunction "S_P$4") (pintype "passive"))
      (node (ref "U$1") (pin "114") (pinfunction "VSS5_114") (pintype "bidirectional"))
      (node (ref "U$1") (pin "133") (pinfunction "VSS6_133") (pintype "bidirectional"))
      (node (ref "U$1") (pin "148") (pinfunction "VSS7_148") (pintype "bidirectional"))
      (node (ref "U$1") (pin "169") (pinfunction "VSS8_169") (pintype "bidirectional"))
      (node (ref "U$1") (pin "172") (pinfunction "VSS(REG)3_172") (pintype "bidirectional"))
      (node (ref "U$1") (pin "189") (pinfunction "VSS9_189") (pintype "bidirectional"))
      (node (ref "U$1") (pin "200") (pinfunction "VSS10_200") (pintype "bidirectional"))
      (node (ref "U$1") (pin "22") (pinfunction "VSSA_22") (pintype "bidirectional"))
      (node (ref "U$1") (pin "32") (pinfunction "VSS(REG)1_32") (pintype "bidirectional"))
      (node (ref "U$1") (pin "33") (pinfunction "VSS1_33") (pintype "bidirectional"))
      (node (ref "U$1") (pin "63") (pinfunction "VSS2_63") (pintype "bidirectional"))
      (node (ref "U$1") (pin "77") (pinfunction "VSS3_77") (pintype "bidirectional"))
      (node (ref "U$1") (pin "84") (pinfunction "VSS(REG)2_84") (pintype "bidirectional"))
      (node (ref "U$1") (pin "93") (pinfunction "VSS4_93") (pintype "bidirectional"))
      (node (ref "U$2") (pin "P$1") (pinfunction "LED-_P$1") (pintype "power_in"))
      (node (ref "U$2") (pin "P$2") (pinfunction "LED-1_P$2") (pintype "power_in"))
      (node (ref "U$2") (pin "P$53") (pinfunction "VSS_P$53") (pintype "power_in"))
      (node (ref "U$2") (pin "P$54") (pinfunction "VSS_P$54") (pintype "power_in"))
      (node (ref "U$3") (pin "DET_B") (pinfunction "DET_B_DET_B") (pintype "bidirectional"))
      (node (ref "U$3") (pin "VSS") (pinfunction "VSS_VSS") (pintype "bidirectional"))
      (node (ref "U$4") (pin "P$2") (pinfunction "P$2_P$2") (pintype "power_in"))
      (node (ref "U1") (pin "1") (pinfunction "PGND_2_1") (pintype "passive"))
      (node (ref "U1") (pin "12") (pinfunction "PGND_3_12") (pintype "passive"))
      (node (ref "U1") (pin "13") (pinfunction "PGND_13") (pintype "passive"))
      (node (ref "U1") (pin "5") (pinfunction "MODE_5") (pintype "input"))
      (node (ref "U1") (pin "7") (pinfunction "SGND_7") (pintype "passive"))
      (node (ref "U2") (pin "2") (pinfunction "GND_2") (pintype "passive"))
      (node (ref "U3") (pin "11") (pinfunction "GND_11") (pintype "passive"))
      (node (ref "U3") (pin "3") (pinfunction "GND_2_3") (pintype "passive"))
      (node (ref "U4") (pin "27") (pinfunction "GND_27") (pintype "power_in"))
      (node (ref "U4") (pin "46") (pinfunction "GND_46") (pintype "power_in"))
      (node (ref "U5") (pin "P$10") (pinfunction "GND_P$10") (pintype "power_in"))
    )
    (net (code "62") (name "KEY_I2C_SCL") (class "Default")
      (node (ref "J10") (pin "P$3") (pinfunction "S3_P$3") (pintype "passive"))
      (node (ref "R30") (pin "2") (pinfunction "2_2") (pintype "passive"))
      (node (ref "U$1") (pin "48") (pinfunction "P0[28]/I2C0_SCL/USB_SCL1_48") (pintype "bidirectional"))
    )
    (net (code "63") (name "KEY_I2C_SDA") (class "Default")
      (node (ref "J10") (pin "P$2") (pinfunction "S2_P$2") (pintype "passive"))
      (node (ref "R29") (pin "2") (pinfunction "2_2") (pintype "passive"))
      (node (ref "U$1") (pin "50") (pinfunction "P0[27]/I2C0_SDA/USB_SDA1_50") (pintype "bidirectional"))
    )
    (net (code "64") (name "KEY_INT") (class "Default")
      (node (ref "J10") (pin "P$4") (pinfunction "S4_P$4") (pintype "passive"))
      (node (ref "U$1") (pin "61") (pinfunction "P0[29]/USB_D+1/EINT_0_61") (pintype "bidirectional"))
    )
    (net (code "65") (name "LCD_DCLK") (class "Default")
      (node (ref "J8") (pin "P$30") (pinfunction "CLK_P$30") (pintype "bidirectional"))
      (node (ref "U$1") (pin "150") (pinfunction "P2[2]/PWM1[3]/U1_CTS/T2_MAT3/TRACEDATA[3]/LCD_DCLK_150") (pintype "bidirectional"))
      (node (ref "U$2") (pin "P$38") (pinfunction "DCLK_P$38") (pintype "bidirectional"))
    )
    (net (code "66") (name "LCD_ENAB_M") (class "Default")
      (node (ref "J8") (pin "P$34") (pinfunction "DE_P$34") (pintype "bidirectional"))
      (node (ref "R8") (pin "1") (pinfunction "1_1") (pintype "passive"))
      (node (ref "U$1") (pin "142") (pinfunction "P2[4]/PWM1[5]/U1_DSR/T2_MAT1/TRACEDATA[1]/LCD_ENAB_M_142") (pintype "bidirectional"))
    )
    (net (code "67") (name "LCD_FP") (class "Default")
      (node (ref "J8") (pin "P$33") (pinfunction "VSYNC_P$33") (pintype "bidirectional"))
      (node (ref "U$1") (pin "144") (pinfunction "P2[3]/PWM1[4]/U1_DCD/T2_MAT2/TRACEDATA[2]/LCD_FP_144") (pintype "bidirectional"))
      (node (ref "U$2") (pin "P$37") (pinfunction "VSYNC_P$37") (pintype "bidirectional"))
    )
    (net (code "68") (name "LCD_LE") (class "Default")
      (node (ref "R9") (pin "1") (pinfunction "1_1") (pintype "passive"))
      (node (ref "U$1") (pin "152") (pinfunction "P2[1]/PWM1[2]/U1_RXD/LCD_LE_152") (pintype "bidirectional"))
    )
    (net (code "69") (name "LCD_LP") (class "Default")
      (node (ref "J8") (pin "P$32") (pinfunction "HSYNC_P$32") (pintype "bidirectional"))
      (node (ref "U$1") (pin "140") (pinfunction "P2[5]/PWM1[6]/U1_DTR/T2_MAT0/TRACEDATA[0]/LCD_LP_140") (pintype "bidirectional"))
      (node (ref "U$2") (pin "P$36") (pinfunction "HSYNC_P$36") (pintype "bidirectional"))
    )
    (net (code "70") (name "LCD_PWR") (class "Default")
      (node (ref "R10") (pin "1") (pinfunction "1_1") (pintype "passive"))
      (node (ref "U$1") (pin "154") (pinfunction "P2[0]/PWM1[1]/U1_TXD/LCD_PWR_154") (pintype "bidirectional"))
    )
    (net (code "71") (name "LED1_PWR") (class "Default")
      (node (ref "J8") (pin "P$2") (pinfunction "LED+_P$2") (pintype "power_in"))
      (node (ref "JP1") (pin "1") (pinfunction "1_1") (pintype "passive"))
      (node (ref "R6") (pin "1") (pinfunction "1_1") (pintype "passive"))
      (node (ref "U$2") (pin "P$3") (pinfunction "LED+_P$3") (pintype "power_in"))
      (node (ref "U3") (pin "1") (pinfunction "LED1_1") (pintype "output"))
    )
    (net (code "72") (name "LED2_PWR") (class "Default")
      (node (ref "JP1") (pin "3") (pinfunction "3_3") (pintype "passive"))
      (node (ref "R7") (pin "1") (pinfunction "1_1") (pintype "passive"))
      (node (ref "U3") (pin "5") (pinfunction "LED2_5") (pintype "output"))
    )
    (net (code "73") (name "LED_CTRL") (class "Default")
      (node (ref "U$1") (pin "185") (pinfunction "P1[2]/ENET_TXD2/SD_CLK/PWM0_1_185") (pintype "bidirectional"))
      (node (ref "U3") (pin "2") (pinfunction "CTRL1_2") (pintype "input"))
      (node (ref "U3") (pin "4") (pinfunction "CTRL2_4") (pintype "input"))
    )
    (net (code "74") (name "Net-(J2-Pad2)") (class "Default")
      (node (ref "J2") (pin "2") (pinfunction "2_2") (pintype "bidirectional"))
      (node (ref "R18") (pin "1") (pinfunction "1_1") (pintype "passive"))
      (node (ref "U$4") (pin "P$6") (pinfunction "P$6_P$6") (pintype "bidirectional"))
    )
    (net (code "75") (name "Net-(J2-Pad3)") (class "Default")
      (node (ref "J2") (pin "3") (pinfunction "3_3") (pintype "bidirectional"))
      (node (ref "R17") (pin "1") (pinfunction "1_1") (pintype "passive"))
      (node (ref "U$4") (pin "P$1") (pinfunction "P$1_P$1") (pintype "bidirectional"))
    )
    (net (code "76") (name "Net-(J4-S3)") (class "Default")
      (node (ref "J4") (pin "3") (pinfunction "S3_3") (pintype "passive"))
      (node (ref "U$1") (pin "94") (pinfunction "P0[0]/CAN_RD1/U3_TXD/I2C1_SDA/U0_TXD_94") (pintype "bidirectional"))
    )
    (net (code "77") (name "Net-(J4-S4)") (class "Default")
      (node (ref "J4") (pin "4") (pinfunction "S4_4") (pintype "passive"))
      (node (ref "U$1") (pin "96") (pinfunction "P0[1]/CAN_TD1/U3_RXD/I2C1_SCL/U0_RXD_96") (pintype "bidirectional"))
    )
    (net (code "78") (name "Net-(J7-S1)") (class "Default")
      (node (ref "J7") (pin "1") (pinfunction "S1_1") (pintype "passive"))
      (node (ref "R21") (pin "1") (pinfunction "1_1") (pintype "passive"))
    )
    (net (code "79") (name "Net-(J11-S5)") (class "Default")
      (node (ref "J11") (pin "5") (pinfunction "S5_5") (pintype "passive"))
      (node (ref "U$1") (pin "9") (pinfunction "P5[0]/EMC_A[24]/T2_MAT2_9") (pintype "bidirectional"))
    )
    (net (code "80") (name "Net-(J11-S7)") (class "Default")
      (node (ref "J11") (pin "7") (pinfunction "S7_7") (pintype "passive"))
      (node (ref "U$1") (pin "30") (pinfunction "P5[1]/EMC_A[25]/T2_MAT3_30") (pintype "bidirectional"))
    )
    (net (code "81") (name "Net-(J11-S13)") (class "Default")
      (node (ref "J11") (pin "13") (pinfunction "S13_13") (pintype "passive"))
      (node (ref "U$1") (pin "206") (pinfunction "P5[4]/U0_OE/T3_MAT3/U4_TXD_206") (pintype "bidirectional"))
    )
    (net (code "82") (name "Net-(LED1-PadA)") (class "Default")
      (node (ref "LED1") (pin "A") (pinfunction "A_A") (pintype "passive"))
      (node (ref "R4") (pin "1") (pinfunction "1_1") (pintype "passive"))
    )
    (net (code "83") (name "Net-(LED2-PadA)") (class "Default")
      (node (ref "LED2") (pin "A") (pinfunction "A_A") (pintype "passive"))
      (node (ref "R16") (pin "1") (pinfunction "1_1") (pintype "passive"))
    )
    (net (code "84") (name "Net-(Q1-B)") (class "Default")
      (node (ref "Q1") (pin "1") (pinfunction "B_1") (pintype "passive"))
      (node (ref "U$1") (pin "69") (pinfunction "P0[14]/~{USB_HSTEN2}/SSP1_SSEL/USB_CONNECT2_69") (pintype "bidirectional"))
    )
    (net (code "85") (name "Net-(Q1-C)") (class "Default")
      (node (ref "Q1") (pin "3") (pinfunction "C_3") (pintype "passive"))
      (node (ref "R15") (pin "2") (pinfunction "2_2") (pintype "passive"))
    )
    (net (code "86") (name "Net-(R9-Pad2)") (class "Default")
      (node (ref "R9") (pin "2") (pinfunction "2_2") (pintype "passive"))
      (node (ref "U$2") (pin "P$50") (pinfunction "NC_P$50") (pintype "bidirectional"))
    )
    (net (code "87") (name "Net-(R10-Pad2)") (class "Default")
      (node (ref "R10") (pin "2") (pinfunction "2_2") (pintype "passive"))
      (node (ref "U$2") (pin "P$51") (pinfunction "NC_P$51") (pintype "bidirectional"))
    )
    (net (code "88") (name "Net-(R14-Pad2)") (class "Default")
      (node (ref "R14") (pin "2") (pinfunction "2_2") (pintype "passive"))
      (node (ref "U$3") (pin "DET_A") (pinfunction "DET_A_DET_A") (pintype "bidirectional"))
    )
    (net (code "89") (name "Net-(U$1A-VDDA)") (class "Default")
      (node (ref "C14") (pin "1") (pinfunction "1_1") (pintype "passive"))
      (node (ref "L4") (pin "2") (pinfunction "2_2") (pintype "passive"))
      (node (ref "U$1") (pin "20") (pinfunction "VDDA_20") (pintype "bidirectional"))
    )
    (net (code "90") (name "Net-(U$1A-VREFP)") (class "Default")
      (node (ref "C15") (pin "1") (pinfunction "1_1") (pintype "passive"))
      (node (ref "L5") (pin "2") (pinfunction "2_2") (pintype "passive"))
      (node (ref "U$1") (pin "24") (pinfunction "VREFP_24") (pintype "bidirectional"))
    )
    (net (code "91") (name "Net-(U$1A-XTAL1)") (class "Default")
      (node (ref "C13") (pin "1") (pinfunction "1_1") (pintype "passive"))
      (node (ref "U$1") (pin "44") (pinfunction "XTAL1_44") (pintype "bidirectional"))
      (node (ref "X1") (pin "1") (pinfunction "1_1") (pintype "passive"))
    )
    (net (code "92") (name "Net-(U$1A-XTAL2)") (class "Default")
      (node (ref "C12") (pin "1") (pinfunction "1_1") (pintype "passive"))
      (node (ref "U$1") (pin "46") (pinfunction "XTAL2_46") (pintype "bidirectional"))
      (node (ref "X1") (pin "2") (pinfunction "2_2") (pintype "passive"))
    )
    (net (code "93") (name "Net-(U$1B-P0[13]{slash}USB_UP_LED2{slash}SSP1_MOSI{slash}ADC0_IN[7])") (class "Default")
      (node (ref "LED2") (pin "C") (pinfunction "C_C") (pintype "passive"))
      (node (ref "U$1") (pin "45") (pinfunction "P0[13]/USB_UP_LED2/SSP1_MOSI/ADC0_IN[7]_45") (pintype "bidirectional"))
    )
    (net (code "94") (name "Net-(U$1B-P0[26]{slash}ADC0_IN[3]{slash}DAC_OUT{slash}U3_RXD)") (class "Default")
      (node (ref "J5") (pin "1") (pinfunction "1_1") (pintype "passive"))
      (node (ref "U$1") (pin "12") (pinfunction "P0[26]/ADC0_IN[3]/DAC_OUT/U3_RXD_12") (pintype "bidirectional"))
    )
    (net (code "95") (name "Net-(U$2-DE)") (class "Default")
      (node (ref "R8") (pin "2") (pinfunction "2_2") (pintype "passive"))
      (node (ref "U$2") (pin "P$52") (pinfunction "DE_P$52") (pintype "bidirectional"))
    )
    (net (code "96") (name "Net-(U$2-LED+1)") (class "Default")
      (node (ref "JP1") (pin "2") (pinfunction "2_2") (pintype "passive"))
      (node (ref "U$2") (pin "P$4") (pinfunction "LED+1_P$4") (pintype "power_in"))
    )
    (net (code "97") (name "Net-(U1-FB)") (class "Default")
      (node (ref "R1") (pin "1") (pinfunction "1_1") (pintype "passive"))
      (node (ref "R2") (pin "2") (pinfunction "2_2") (pintype "passive"))
      (node (ref "U1") (pin "8") (pinfunction "FB_8") (pintype "input"))
    )
    (net (code "98") (name "Net-(U1-PROG)") (class "Default")
      (node (ref "R3") (pin "2") (pinfunction "2_2") (pintype "passive"))
      (node (ref "U1") (pin "6") (pinfunction "PROG_6") (pintype "input"))
    )
    (net (code "99") (name "Net-(U1-SW1)") (class "Default")
      (node (ref "L1") (pin "2") (pinfunction "2_2") (pintype "passive"))
      (node (ref "U1") (pin "2") (pinfunction "SW1_2") (pintype "passive"))
    )
    (net (code "100") (name "Net-(U1-SW2)") (class "Default")
      (node (ref "L1") (pin "1") (pinfunction "1_1") (pintype "passive"))
      (node (ref "U1") (pin "11") (pinfunction "SW2_11") (pintype "passive"))
    )
    (net (code "101") (name "Net-(U1-VC)") (class "Default")
      (node (ref "C2") (pin "1") (pinfunction "1_1") (pintype "passive"))
      (node (ref "R5") (pin "2") (pinfunction "2_2") (pintype "passive"))
      (node (ref "U1") (pin "9") (pinfunction "VC_9") (pintype "output"))
    )
    (net (code "102") (name "Net-(U2-~{POK})") (class "Default")
      (node (ref "LED1") (pin "C") (pinfunction "C_C") (pintype "passive"))
      (node (ref "U2") (pin "3") (pinfunction "~{POK}_3") (pintype "passive"))
    )
    (net (code "103") (name "Net-(U3-CAP1)") (class "Default")
      (node (ref "C9") (pin "1") (pinfunction "1_1") (pintype "passive"))
      (node (ref "R6") (pin "2") (pinfunction "2_2") (pintype "passive"))
      (node (ref "U3") (pin "10") (pinfunction "CAP1_10") (pintype "input"))
    )
    (net (code "104") (name "Net-(U3-CAP2)") (class "Default")
      (node (ref "C11") (pin "1") (pinfunction "1_1") (pintype "passive"))
      (node (ref "R7") (pin "2") (pinfunction "2_2") (pintype "passive"))
      (node (ref "U3") (pin "6") (pinfunction "CAP2_6") (pintype "input"))
    )
    (net (code "105") (name "Net-(U3-SW1)") (class "Default")
      (node (ref "L2") (pin "2") (pinfunction "2_2") (pintype "passive"))
      (node (ref "U3") (pin "9") (pinfunction "SW1_9") (pintype "passive"))
    )
    (net (code "106") (name "Net-(U3-SW2)") (class "Default")
      (node (ref "L3") (pin "2") (pinfunction "2_2") (pintype "passive"))
      (node (ref "U3") (pin "7") (pinfunction "SW2_7") (pintype "passive"))
    )
    (net (code "107") (name "Net-(U4-CE)") (class "Default")
      (node (ref "R19") (pin "2") (pinfunction "2_2") (pintype "passive"))
      (node (ref "U4") (pin "12") (pinfunction "CE_12") (pintype "input"))
    )
    (net (code "108") (name "Net-(U4-~{BYTE})") (class "Default")
      (node (ref "R20") (pin "2") (pinfunction "2_2") (pintype "passive"))
      (node (ref "U4") (pin "47") (pinfunction "~{BYTE}_47") (pintype "input"))
    )
    (net (code "109") (name "Net-(U5-HOLD#{slash}IO3)") (class "Default")
      (node (ref "R28") (pin "2") (pinfunction "2_2") (pintype "passive"))
      (node (ref "U5") (pin "P$1") (pinfunction "HOLD#/IO3_P$1") (pintype "bidirectional"))
    )
    (net (code "110") (name "Net-(U5-W#{slash}ACC{slash}IO2)") (class "Default")
      (node (ref "R22") (pin "2") (pinfunction "2_2") (pintype "passive"))
      (node (ref "U5") (pin "P$9") (pinfunction "W#/ACC/IO2_P$9") (pintype "bidirectional"))
    )
    (net (code "111") (name "R0") (class "Default")
      (node (ref "J8") (pin "P$5") (pinfunction "R0_P$5") (pintype "bidirectional"))
      (node (ref "U$1") (pin "168") (pinfunction "P0[4]/I2S_RX_SCK/CAN_RD_2/T2_CAP0/LCD_VD[0]_168") (pintype "bidirectional"))
      (node (ref "U$2") (pin "P$28") (pinfunction "R0_P$28") (pintype "bidirectional"))
    )
    (net (code "112") (name "R1") (class "Default")
      (node (ref "J8") (pin "P$6") (pinfunction "R1_P$6") (pintype "bidirectional"))
      (node (ref "U$1") (pin "166") (pinfunction "P0[5]/I2S_RX_WS/CAN_TD_2/T2_CAP1/LCD_VD[1]_166") (pintype "bidirectional"))
      (node (ref "U$2") (pin "P$29") (pinfunction "R1_P$29") (pintype "bidirectional"))
    )
    (net (code "113") (name "R2") (class "Default")
      (node (ref "J8") (pin "P$7") (pinfunction "R2_P$7") (pintype "bidirectional"))
      (node (ref "U$1") (pin "134") (pinfunction "P2[8]/CAN_TD2/U2_TXD/U1_CTS/ENET_MDC/LCD_VD[2]/LCD_VD[6]_134") (pintype "bidirectional"))
      (node (ref "U$2") (pin "P$30") (pinfunction "R2_P$30") (pintype "bidirectional"))
    )
    (net (code "114") (name "R3") (class "Default")
      (node (ref "J8") (pin "P$8") (pinfunction "R3_P$8") (pintype "bidirectional"))
      (node (ref "U$1") (pin "132") (pinfunction "P2[9]/USB_CONNECT1/U2_RXD/U4_RXD/ENET_MDIO/LCD_VD[3]/LCD_VD[7]_132") (pintype "bidirectional"))
      (node (ref "U$2") (pin "P$31") (pinfunction "R3_P$31") (pintype "bidirectional"))
    )
    (net (code "115") (name "R4") (class "Default")
      (node (ref "J8") (pin "P$9") (pinfunction "R4_P$9") (pintype "bidirectional"))
      (node (ref "U$1") (pin "138") (pinfunction "P2[6]/PWM1_CAP0/U1_RI/T2_CAP0/U2_OE/TRACECLK/LCD_VD[0]/LCD_VD[4]_138") (pintype "bidirectional"))
      (node (ref "U$2") (pin "P$32") (pinfunction "R4_P$32") (pintype "bidirectional"))
    )
    (net (code "116") (name "R5") (class "Default")
      (node (ref "J8") (pin "P$10") (pinfunction "R5_P$10") (pintype "bidirectional"))
      (node (ref "U$1") (pin "136") (pinfunction "P2[7]/CAN_RD2/U1_RTS/LCD_VD[1]/LCD_VD[5]_136") (pintype "bidirectional"))
      (node (ref "U$2") (pin "P$33") (pinfunction "R5_P$33") (pintype "bidirectional"))
    )
    (net (code "117") (name "R6") (class "Default")
      (node (ref "J8") (pin "P$11") (pinfunction "R6_P$11") (pintype "bidirectional"))
      (node (ref "U$1") (pin "70") (pinfunction "P1[20]/USB_TX_DP1/PWM1_2/QEI_PHA/MC_FB0/SSP0_SCK/LCD_VD[6]/LCD_VD[10]_70") (pintype "bidirectional"))
      (node (ref "U$2") (pin "P$34") (pinfunction "R6_P$34") (pintype "bidirectional"))
    )
    (net (code "118") (name "R7") (class "Default")
      (node (ref "J8") (pin "P$12") (pinfunction "R7_P$12") (pintype "bidirectional"))
      (node (ref "U$1") (pin "72") (pinfunction "P1[21]/USB_TX_DM1/PWM1_3/SSP0_SSEL/~{MC_ABORT}/LCD_VD[7]/LCD_VD[11]_72") (pintype "bidirectional"))
      (node (ref "U$2") (pin "P$35") (pinfunction "R7_P$35") (pintype "bidirectional"))
    )
    (net (code "119") (name "SCL") (class "Default")
      (node (ref "J11") (pin "11") (pinfunction "S11_11") (pintype "passive"))
      (node (ref "R13") (pin "2") (pinfunction "2_2") (pintype "passive"))
      (node (ref "U$1") (pin "141") (pinfunction "P5[3]/U4_RXD/I2C0_SCL_141") (pintype "bidirectional"))
    )
    (net (code "120") (name "SDA") (class "Default")
      (node (ref "J11") (pin "9") (pinfunction "S9_9") (pintype "passive"))
      (node (ref "R12") (pin "2") (pinfunction "2_2") (pintype "passive"))
      (node (ref "U$1") (pin "117") (pinfunction "P5[2]/T3_MAT2/I2C0_SDA_117") (pintype "bidirectional"))
    )
    (net (code "121") (name "SD_CLK") (class "Default")
      (node (ref "U$1") (pin "122") (pinfunction "P0[19]/U1_DSR/SD_CLK/I2C1_SDA_122") (pintype "bidirectional"))
      (node (ref "U$3") (pin "CLK") (pinfunction "CLK_CLK") (pintype "bidirectional"))
    )
    (net (code "122") (name "SD_CMD") (class "Default")
      (node (ref "U$1") (pin "120") (pinfunction "P0[20]/U1_DTR/SD_CMD/I2C1_SCL_120") (pintype "bidirectional"))
      (node (ref "U$3") (pin "CMD") (pinfunction "CMD_CMD") (pintype "bidirectional"))
    )
    (net (code "123") (name "SD_DAT_0") (class "Default")
      (node (ref "U$1") (pin "116") (pinfunction "P0[22]/U1_RTS/SD_DAT[0]/U4_TXD/CAN_TD1_116") (pintype "bidirectional"))
      (node (ref "U$3") (pin "DAT0") (pinfunction "DAT0_DAT0") (pintype "bidirectional"))
    )
    (net (code "124") (name "SD_DAT_1") (class "Default")
      (node (ref "U$1") (pin "153") (pinfunction "P1[7]/ENET_COL/SD_DAT[1]/PWM0_5_153") (pintype "bidirectional"))
      (node (ref "U$3") (pin "DAT1") (pinfunction "DAT1_DAT1") (pintype "bidirectional"))
    )
    (net (code "125") (name "SD_DAT_2") (class "Default")
      (node (ref "U$1") (pin "163") (pinfunction "P1[11]/ENET_RXD2/SD_DAT[2]/PWM0_6_163") (pintype "bidirectional"))
      (node (ref "U$3") (pin "DAT2") (pinfunction "DAT2_DAT2") (pintype "bidirectional"))
    )
    (net (code "126") (name "SD_DAT_3") (class "Default")
      (node (ref "U$1") (pin "157") (pinfunction "P1[12]/ENET_RXD3/SD_DAT[3]/PWM0_CAP0_157") (pintype "bidirectional"))
      (node (ref "U$3") (pin "CD/DAT3") (pinfunction "CD/DAT3_CD/DAT3") (pintype "bidirectional"))
    )
    (net (code "127") (name "SPI_CS") (class "Default")
      (node (ref "J11") (pin "12") (pinfunction "S12_12") (pintype "passive"))
      (node (ref "U$1") (pin "190") (pinfunction "P1[8]/ENET_CRS/T3_MAT1/SSP2_SSEL_190") (pintype "bidirectional"))
    )
    (net (code "128") (name "SPI_FLASH_CS") (class "Default")
      (node (ref "U$1") (pin "130") (pinfunction "P0[16]/U1_RXD/SSP0_SSEL_130") (pintype "bidirectional"))
      (node (ref "U5") (pin "P$7") (pinfunction "CS#_P$7") (pintype "input"))
    )
    (net (code "129") (name "SPI_FLASH_MISO") (class "Default")
      (node (ref "U$1") (pin "126") (pinfunction "P0[17]/U1_CTS/SSP0_MISO_126") (pintype "bidirectional"))
      (node (ref "U5") (pin "P$8") (pinfunction "SO/IO1_P$8") (pintype "bidirectional"))
    )
    (net (code "130") (name "SPI_FLASH_MOSI") (class "Default")
      (node (ref "U$1") (pin "124") (pinfunction "P0[18]/U1_DCD/SSP0_MOSI_124") (pintype "bidirectional"))
      (node (ref "U5") (pin "P$15") (pinfunction "SI/IO0_P$15") (pintype "bidirectional"))
    )
    (net (code "131") (name "SPI_FLASH_SCK") (class "Default")
      (node (ref "U$1") (pin "128") (pinfunction "P0[15]/U1_TXD/SSP0_SCK_128") (pintype "bidirectional"))
      (node (ref "U5") (pin "P$16") (pinfunction "SCK_P$16") (pintype "input"))
    )
    (net (code "132") (name "SPI_MISO") (class "Default")
      (node (ref "J11") (pin "10") (pinfunction "S10_10") (pintype "passive"))
      (node (ref "U$1") (pin "192") (pinfunction "P1[4]/ENET_TX_EN/T3_MAT2/SSP2_MISO_192") (pintype "bidirectional"))
    )
    (net (code "133") (name "SPI_MOSI") (class "Default")
      (node (ref "J11") (pin "8") (pinfunction "S8_8") (pintype "passive"))
      (node (ref "U$1") (pin "194") (pinfunction "P1[1]/ENET_TXD1/T3_MAT3/SSP2_MOSI_194") (pintype "bidirectional"))
    )
    (net (code "134") (name "SPI_SCK") (class "Default")
      (node (ref "J11") (pin "6") (pinfunction "S6_6") (pintype "passive"))
      (node (ref "U$1") (pin "196") (pinfunction "P1[0]/ENET_TXD0/T3_CAP1/SSP2_SCK_196") (pintype "bidirectional"))
    )
    (net (code "135") (name "TCK{slash}SWDCLK") (class "Default")
      (node (ref "J6") (pin "P$4") (pinfunction "S4_P$4") (pintype "passive"))
      (node (ref "J7") (pin "3") (pinfunction "S3_3") (pintype "passive"))
      (node (ref "R24") (pin "1") (pinfunction "1_1") (pintype "passive"))
      (node (ref "U$1") (pin "10") (pinfunction "JTAG_TCK(SWDCLK)_10") (pintype "bidirectional"))
    )
    (net (code "136") (name "TDI") (class "Default")
      (node (ref "J6") (pin "P$8") (pinfunction "S8_P$8") (pintype "passive"))
      (node (ref "J7") (pin "5") (pinfunction "S5_5") (pintype "passive"))
      (node (ref "R26") (pin "2") (pinfunction "2_2") (pintype "passive"))
      (node (ref "U$1") (pin "4") (pinfunction "JTAG_TDI_4") (pintype "bidirectional"))
    )
    (net (code "137") (name "TDO{slash}SWO") (class "Default")
      (node (ref "J6") (pin "P$6") (pinfunction "S6_P$6") (pintype "passive"))
      (node (ref "J7") (pin "4") (pinfunction "S4_4") (pintype "passive"))
      (node (ref "R25") (pin "2") (pinfunction "2_2") (pintype "passive"))
      (node (ref "U$1") (pin "2") (pinfunction "JTAG_TDO(SWO)_2") (pintype "bidirectional"))
    )
    (net (code "138") (name "TMS{slash}SWDIO") (class "Default")
      (node (ref "J6") (pin "P$2") (pinfunction "S2_P$2") (pintype "passive"))
      (node (ref "J7") (pin "2") (pinfunction "S2_2") (pintype "passive"))
      (node (ref "R23") (pin "2") (pinfunction "2_2") (pintype "passive"))
      (node (ref "U$1") (pin "6") (pinfunction "JTAG_TMS(SWDIO)_6") (pintype "bidirectional"))
    )
    (net (code "139") (name "TRST") (class "Default")
      (node (ref "R27") (pin "2") (pinfunction "2_2") (pintype "passive"))
      (node (ref "U$1") (pin "8") (pinfunction "~{JTAG_TRST}_8") (pintype "bidirectional"))
    )
    (net (code "140") (name "USB_D+") (class "Default")
      (node (ref "C17") (pin "1") (pinfunction "1_1") (pintype "passive"))
      (node (ref "R15") (pin "1") (pinfunction "1_1") (pintype "passive"))
      (node (ref "R17") (pin "2") (pinfunction "2_2") (pintype "passive"))
      (node (ref "U$1") (pin "51") (pinfunction "P0[31]/USB_D+2_51") (pintype "bidirectional"))
    )
    (net (code "141") (name "USB_D-") (class "Default")
      (node (ref "C18") (pin "1") (pinfunction "1_1") (pintype "passive"))
      (node (ref "R18") (pin "2") (pinfunction "2_2") (pintype "passive"))
      (node (ref "U$1") (pin "52") (pinfunction "USB_D-2_52") (pintype "bidirectional"))
    )
    (net (code "142") (name "V+") (class "Default")
      (node (ref "C3") (pin "1") (pinfunction "1_1") (pintype "passive"))
      (node (ref "J1") (pin "1") (pinfunction "1_1") (pintype "passive"))
      (node (ref "U2") (pin "4") (pinfunction "DC_4") (pintype "passive"))
    )
    (net (code "143") (name "unconnected-(J2-Pad4)") (class "Default")
      (node (ref "J2") (pin "4") (pinfunction "4_4") (pintype "bidirectional"))
    )
    (net (code "144") (name "unconnected-(J6-S7-PadP$7)") (class "Default")
      (node (ref "J6") (pin "P$7") (pinfunction "S7_P$7") (pintype "passive"))
    )
    (net (code "145") (name "unconnected-(J7-S7-Pad7)") (class "Default")
      (node (ref "J7") (pin "7") (pinfunction "S7_7") (pintype "passive"))
    )
    (net (code "146") (name "unconnected-(J8-DISP-PadP$31)") (class "Default")
      (node (ref "J8") (pin "P$31") (pinfunction "DISP_P$31") (pintype "bidirectional"))
    )
    (net (code "147") (name "unconnected-(J9-S3-PadP$3)") (class "Default")
      (node (ref "J9") (pin "P$3") (pinfunction "S3_P$3") (pintype "passive"))
    )
    (net (code "148") (name "unconnected-(J9-S4-PadP$4)") (class "Default")
      (node (ref "J9") (pin "P$4") (pinfunction "S4_P$4") (pintype "passive"))
    )
    (net (code "149") (name "unconnected-(J9-S5-PadP$5)") (class "Default")
      (node (ref "J9") (pin "P$5") (pinfunction "S5_P$5") (pintype "passive"))
    )
    (net (code "150") (name "unconnected-(J9-S6-PadP$6)") (class "Default")
      (node (ref "J9") (pin "P$6") (pinfunction "S6_P$6") (pintype "passive"))
    )
    (net (code "151") (name "unconnected-(J9-S7-PadP$7)") (class "Default")
      (node (ref "J9") (pin "P$7") (pinfunction "S7_P$7") (pintype "passive"))
    )
    (net (code "152") (name "unconnected-(J9-S8-PadP$8)") (class "Default")
      (node (ref "J9") (pin "P$8") (pinfunction "S8_P$8") (pintype "passive"))
    )
    (net (code "153") (name "unconnected-(J9-S9-PadP$9)") (class "Default")
      (node (ref "J9") (pin "P$9") (pinfunction "S9_P$9") (pintype "passive"))
    )
    (net (code "154") (name "unconnected-(J9-S10-PadP$10)") (class "Default")
      (node (ref "J9") (pin "P$10") (pinfunction "S10_P$10") (pintype "passive"))
    )
    (net (code "155") (name "unconnected-(J9-S11-PadP$11)") (class "Default")
      (node (ref "J9") (pin "P$11") (pinfunction "S11_P$11") (pintype "passive"))
    )
    (net (code "156") (name "unconnected-(J9-S12-PadP$12)") (class "Default")
      (node (ref "J9") (pin "P$12") (pinfunction "S12_P$12") (pintype "passive"))
    )
    (net (code "157") (name "unconnected-(J9-S13-PadP$13)") (class "Default")
      (node (ref "J9") (pin "P$13") (pinfunction "S13_P$13") (pintype "passive"))
    )
    (net (code "158") (name "unconnected-(J9-S14-PadP$14)") (class "Default")
      (node (ref "J9") (pin "P$14") (pinfunction "S14_P$14") (pintype "passive"))
    )
    (net (code "159") (name "unconnected-(J9-S15-PadP$15)") (class "Default")
      (node (ref "J9") (pin "P$15") (pinfunction "S15_P$15") (pintype "passive"))
    )
    (net (code "160") (name "unconnected-(J9-S16-PadP$16)") (class "Default")
      (node (ref "J9") (pin "P$16") (pinfunction "S16_P$16") (pintype "passive"))
    )
    (net (code "161") (name "unconnected-(J9-S17-PadP$17)") (class "Default")
      (node (ref "J9") (pin "P$17") (pinfunction "S17_P$17") (pintype "passive"))
    )
    (net (code "162") (name "unconnected-(J9-S18-PadP$18)") (class "Default")
      (node (ref "J9") (pin "P$18") (pinfunction "S18_P$18") (pintype "passive"))
    )
    (net (code "163") (name "unconnected-(J9-S19-PadP$19)") (class "Default")
      (node (ref "J9") (pin "P$19") (pinfunction "S19_P$19") (pintype "passive"))
    )
    (net (code "164") (name "unconnected-(J9-S20-PadP$20)") (class "Default")
      (node (ref "J9") (pin "P$20") (pinfunction "S20_P$20") (pintype "passive"))
    )
    (net (code "165") (name "unconnected-(J9-S21-PadP$21)") (class "Default")
      (node (ref "J9") (pin "P$21") (pinfunction "S21_P$21") (pintype "passive"))
    )
    (net (code "166") (name "unconnected-(J9-S22-PadP$22)") (class "Default")
      (node (ref "J9") (pin "P$22") (pinfunction "S22_P$22") (pintype "passive"))
    )
    (net (code "167") (name "unconnected-(J9-S23-PadP$23)") (class "Default")
      (node (ref "J9") (pin "P$23") (pinfunction "S23_P$23") (pintype "passive"))
    )
    (net (code "168") (name "unconnected-(J9-S24-PadP$24)") (class "Default")
      (node (ref "J9") (pin "P$24") (pinfunction "S24_P$24") (pintype "passive"))
    )
    (net (code "169") (name "unconnected-(J9-S25-PadP$25)") (class "Default")
      (node (ref "J9") (pin "P$25") (pinfunction "S25_P$25") (pintype "passive"))
    )
    (net (code "170") (name "unconnected-(J9-S26-PadP$26)") (class "Default")
      (node (ref "J9") (pin "P$26") (pinfunction "S26_P$26") (pintype "passive"))
    )
    (net (code "171") (name "unconnected-(J9-S27-PadP$27)") (class "Default")
      (node (ref "J9") (pin "P$27") (pinfunction "S27_P$27") (pintype "passive"))
    )
    (net (code "172") (name "unconnected-(J9-S28-PadP$28)") (class "Default")
      (node (ref "J9") (pin "P$28") (pinfunction "S28_P$28") (pintype "passive"))
    )
    (net (code "173") (name "unconnected-(J9-S29-PadP$29)") (class "Default")
      (node (ref "J9") (pin "P$29") (pinfunction "S29_P$29") (pintype "passive"))
    )
    (net (code "174") (name "unconnected-(J9-S30-PadP$30)") (class "Default")
      (node (ref "J9") (pin "P$30") (pinfunction "S30_P$30") (pintype "passive"))
    )
    (net (code "175") (name "unconnected-(J9-S31-PadP$31)") (class "Default")
      (node (ref "J9") (pin "P$31") (pinfunction "S31_P$31") (pintype "passive"))
    )
    (net (code "176") (name "unconnected-(J9-S32-PadP$32)") (class "Default")
      (node (ref "J9") (pin "P$32") (pinfunction "S32_P$32") (pintype "passive"))
    )
    (net (code "177") (name "unconnected-(J9-S33-PadP$33)") (class "Default")
      (node (ref "J9") (pin "P$33") (pinfunction "S33_P$33") (pintype "passive"))
    )
    (net (code "178") (name "unconnected-(J9-S34-PadP$34)") (class "Default")
      (node (ref "J9") (pin "P$34") (pinfunction "S34_P$34") (pintype "passive"))
    )
    (net (code "179") (name "unconnected-(J9-S35-PadP$35)") (class "Default")
      (node (ref "J9") (pin "P$35") (pinfunction "S35_P$35") (pintype "passive"))
    )
    (net (code "180") (name "unconnected-(J9-S36-PadP$36)") (class "Default")
      (node (ref "J9") (pin "P$36") (pinfunction "S36_P$36") (pintype "passive"))
    )
    (net (code "181") (name "unconnected-(J9-S37-PadP$37)") (class "Default")
      (node (ref "J9") (pin "P$37") (pinfunction "S37_P$37") (pintype "passive"))
    )
    (net (code "182") (name "unconnected-(J9-S38-PadP$38)") (class "Default")
      (node (ref "J9") (pin "P$38") (pinfunction "S38_P$38") (pintype "passive"))
    )
    (net (code "183") (name "unconnected-(J9-S39-PadP$39)") (class "Default")
      (node (ref "J9") (pin "P$39") (pinfunction "S39_P$39") (pintype "passive"))
    )
    (net (code "184") (name "unconnected-(J9-S40-PadP$40)") (class "Default")
      (node (ref "J9") (pin "P$40") (pinfunction "S40_P$40") (pintype "passive"))
    )
    (net (code "185") (name "unconnected-(J9-S41-PadP$41)") (class "Default")
      (node (ref "J9") (pin "P$41") (pinfunction "S41_P$41") (pintype "passive"))
    )
    (net (code "186") (name "unconnected-(J9-S42-PadP$42)") (class "Default")
      (node (ref "J9") (pin "P$42") (pinfunction "S42_P$42") (pintype "passive"))
    )
    (net (code "187") (name "unconnected-(J9-S43-PadP$43)") (class "Default")
      (node (ref "J9") (pin "P$43") (pinfunction "S43_P$43") (pintype "passive"))
    )
    (net (code "188") (name "unconnected-(J9-S44-PadP$44)") (class "Default")
      (node (ref "J9") (pin "P$44") (pinfunction "S44_P$44") (pintype "passive"))
    )
    (net (code "189") (name "unconnected-(J9-S45-PadP$45)") (class "Default")
      (node (ref "J9") (pin "P$45") (pinfunction "S45_P$45") (pintype "passive"))
    )
    (net (code "190") (name "unconnected-(J9-S46-PadP$46)") (class "Default")
      (node (ref "J9") (pin "P$46") (pinfunction "S46_P$46") (pintype "passive"))
    )
    (net (code "191") (name "unconnected-(J9-S47-PadP$47)") (class "Default")
      (node (ref "J9") (pin "P$47") (pinfunction "S47_P$47") (pintype "passive"))
    )
    (net (code "192") (name "unconnected-(J9-S48-PadP$48)") (class "Default")
      (node (ref "J9") (pin "P$48") (pinfunction "S48_P$48") (pintype "passive"))
    )
    (net (code "193") (name "unconnected-(J11-S15-Pad15)") (class "Default")
      (node (ref "J11") (pin "15") (pinfunction "S15_15") (pintype "passive"))
    )
    (net (code "194") (name "unconnected-(J12-S3-PadP$3)") (class "Default")
      (node (ref "J12") (pin "P$3") (pinfunction "S3_P$3") (pintype "passive"))
    )
    (net (code "195") (name "unconnected-(J12-S4-PadP$4)") (class "Default")
      (node (ref "J12") (pin "P$4") (pinfunction "S4_P$4") (pintype "passive"))
    )
    (net (code "196") (name "unconnected-(J12-S5-PadP$5)") (class "Default")
      (node (ref "J12") (pin "P$5") (pinfunction "S5_P$5") (pintype "passive"))
    )
    (net (code "197") (name "unconnected-(J12-S6-PadP$6)") (class "Default")
      (node (ref "J12") (pin "P$6") (pinfunction "S6_P$6") (pintype "passive"))
    )
    (net (code "198") (name "unconnected-(J12-S7-PadP$7)") (class "Default")
      (node (ref "J12") (pin "P$7") (pinfunction "S7_P$7") (pintype "passive"))
    )
    (net (code "199") (name "unconnected-(J12-S8-PadP$8)") (class "Default")
      (node (ref "J12") (pin "P$8") (pinfunction "S8_P$8") (pintype "passive"))
    )
    (net (code "200") (name "unconnected-(J12-S9-PadP$9)") (class "Default")
      (node (ref "J12") (pin "P$9") (pinfunction "S9_P$9") (pintype "passive"))
    )
    (net (code "201") (name "unconnected-(J12-S10-PadP$10)") (class "Default")
      (node (ref "J12") (pin "P$10") (pinfunction "S10_P$10") (pintype "passive"))
    )
    (net (code "202") (name "unconnected-(J12-S11-PadP$11)") (class "Default")
      (node (ref "J12") (pin "P$11") (pinfunction "S11_P$11") (pintype "passive"))
    )
    (net (code "203") (name "unconnected-(J12-S12-PadP$12)") (class "Default")
      (node (ref "J12") (pin "P$12") (pinfunction "S12_P$12") (pintype "passive"))
    )
    (net (code "204") (name "unconnected-(J12-S13-PadP$13)") (class "Default")
      (node (ref "J12") (pin "P$13") (pinfunction "S13_P$13") (pintype "passive"))
    )
    (net (code "205") (name "unconnected-(J12-S14-PadP$14)") (class "Default")
      (node (ref "J12") (pin "P$14") (pinfunction "S14_P$14") (pintype "passive"))
    )
    (net (code "206") (name "unconnected-(J12-S15-PadP$15)") (class "Default")
      (node (ref "J12") (pin "P$15") (pinfunction "S15_P$15") (pintype "passive"))
    )
    (net (code "207") (name "unconnected-(J12-S16-PadP$16)") (class "Default")
      (node (ref "J12") (pin "P$16") (pinfunction "S16_P$16") (pintype "passive"))
    )
    (net (code "208") (name "unconnected-(J12-S17-PadP$17)") (class "Default")
      (node (ref "J12") (pin "P$17") (pinfunction "S17_P$17") (pintype "passive"))
    )
    (net (code "209") (name "unconnected-(J12-S18-PadP$18)") (class "Default")
      (node (ref "J12") (pin "P$18") (pinfunction "S18_P$18") (pintype "passive"))
    )
    (net (code "210") (name "unconnected-(J12-S19-PadP$19)") (class "Default")
      (node (ref "J12") (pin "P$19") (pinfunction "S19_P$19") (pintype "passive"))
    )
    (net (code "211") (name "unconnected-(J12-S20-PadP$20)") (class "Default")
      (node (ref "J12") (pin "P$20") (pinfunction "S20_P$20") (pintype "passive"))
    )
    (net (code "212") (name "unconnected-(J12-S21-PadP$21)") (class "Default")
      (node (ref "J12") (pin "P$21") (pinfunction "S21_P$21") (pintype "passive"))
    )
    (net (code "213") (name "unconnected-(J12-S22-PadP$22)") (class "Default")
      (node (ref "J12") (pin "P$22") (pinfunction "S22_P$22") (pintype "passive"))
    )
    (net (code "214") (name "unconnected-(J12-S23-PadP$23)") (class "Default")
      (node (ref "J12") (pin "P$23") (pinfunction "S23_P$23") (pintype "passive"))
    )
    (net (code "215") (name "unconnected-(J12-S24-PadP$24)") (class "Default")
      (node (ref "J12") (pin "P$24") (pinfunction "S24_P$24") (pintype "passive"))
    )
    (net (code "216") (name "unconnected-(J12-S25-PadP$25)") (class "Default")
      (node (ref "J12") (pin "P$25") (pinfunction "S25_P$25") (pintype "passive"))
    )
    (net (code "217") (name "unconnected-(J12-S26-PadP$26)") (class "Default")
      (node (ref "J12") (pin "P$26") (pinfunction "S26_P$26") (pintype "passive"))
    )
    (net (code "218") (name "unconnected-(J12-S27-PadP$27)") (class "Default")
      (node (ref "J12") (pin "P$27") (pinfunction "S27_P$27") (pintype "passive"))
    )
    (net (code "219") (name "unconnected-(J12-S28-PadP$28)") (class "Default")
      (node (ref "J12") (pin "P$28") (pinfunction "S28_P$28") (pintype "passive"))
    )
    (net (code "220") (name "unconnected-(J12-S29-PadP$29)") (class "Default")
      (node (ref "J12") (pin "P$29") (pinfunction "S29_P$29") (pintype "passive"))
    )
    (net (code "221") (name "unconnected-(J12-S30-PadP$30)") (class "Default")
      (node (ref "J12") (pin "P$30") (pinfunction "S30_P$30") (pintype "passive"))
    )
    (net (code "222") (name "unconnected-(J12-S31-PadP$31)") (class "Default")
      (node (ref "J12") (pin "P$31") (pinfunction "S31_P$31") (pintype "passive"))
    )
    (net (code "223") (name "unconnected-(J12-S32-PadP$32)") (class "Default")
      (node (ref "J12") (pin "P$32") (pinfunction "S32_P$32") (pintype "passive"))
    )
    (net (code "224") (name "unconnected-(J12-S33-PadP$33)") (class "Default")
      (node (ref "J12") (pin "P$33") (pinfunction "S33_P$33") (pintype "passive"))
    )
    (net (code "225") (name "unconnected-(J12-S34-PadP$34)") (class "Default")
      (node (ref "J12") (pin "P$34") (pinfunction "S34_P$34") (pintype "passive"))
    )
    (net (code "226") (name "unconnected-(J12-S35-PadP$35)") (class "Default")
      (node (ref "J12") (pin "P$35") (pinfunction "S35_P$35") (pintype "passive"))
    )
    (net (code "227") (name "unconnected-(J12-S36-PadP$36)") (class "Default")
      (node (ref "J12") (pin "P$36") (pinfunction "S36_P$36") (pintype "passive"))
    )
    (net (code "228") (name "unconnected-(J12-S37-PadP$37)") (class "Default")
      (node (ref "J12") (pin "P$37") (pinfunction "S37_P$37") (pintype "passive"))
    )
    (net (code "229") (name "unconnected-(J12-S38-PadP$38)") (class "Default")
      (node (ref "J12") (pin "P$38") (pinfunction "S38_P$38") (pintype "passive"))
    )
    (net (code "230") (name "unconnected-(J12-S39-PadP$39)") (class "Default")
      (node (ref "J12") (pin "P$39") (pinfunction "S39_P$39") (pintype "passive"))
    )
    (net (code "231") (name "unconnected-(J12-S40-PadP$40)") (class "Default")
      (node (ref "J12") (pin "P$40") (pinfunction "S40_P$40") (pintype "passive"))
    )
    (net (code "232") (name "unconnected-(J12-S41-PadP$41)") (class "Default")
      (node (ref "J12") (pin "P$41") (pinfunction "S41_P$41") (pintype "passive"))
    )
    (net (code "233") (name "unconnected-(J12-S42-PadP$42)") (class "Default")
      (node (ref "J12") (pin "P$42") (pinfunction "S42_P$42") (pintype "passive"))
    )
    (net (code "234") (name "unconnected-(J12-S43-PadP$43)") (class "Default")
      (node (ref "J12") (pin "P$43") (pinfunction "S43_P$43") (pintype "passive"))
    )
    (net (code "235") (name "unconnected-(J12-S44-PadP$44)") (class "Default")
      (node (ref "J12") (pin "P$44") (pinfunction "S44_P$44") (pintype "passive"))
    )
    (net (code "236") (name "unconnected-(J12-S45-PadP$45)") (class "Default")
      (node (ref "J12") (pin "P$45") (pinfunction "S45_P$45") (pintype "passive"))
    )
    (net (code "237") (name "unconnected-(J12-S46-PadP$46)") (class "Default")
      (node (ref "J12") (pin "P$46") (pinfunction "S46_P$46") (pintype "passive"))
    )
    (net (code "238") (name "unconnected-(J12-S47-PadP$47)") (class "Default")
      (node (ref "J12") (pin "P$47") (pinfunction "S47_P$47") (pintype "passive"))
    )
    (net (code "239") (name "unconnected-(J12-S48-PadP$48)") (class "Default")
      (node (ref "J12") (pin "P$48") (pinfunction "S48_P$48") (pintype "passive"))
    )
    (net (code "240") (name "unconnected-(U$1A-RTCX1-Pad34)") (class "Default")
      (node (ref "U$1") (pin "34") (pinfunction "RTCX1_34") (pintype "bidirectional"))
    )
    (net (code "241") (name "unconnected-(U$1A-RTCX2-Pad36)") (class "Default")
      (node (ref "U$1") (pin "36") (pinfunction "RTCX2_36") (pintype "bidirectional"))
    )
    (net (code "242") (name "unconnected-(U$1A-RTC_ALARM-Pad37)") (class "Default")
      (node (ref "U$1") (pin "37") (pinfunction "RTC_ALARM_37") (pintype "bidirectional"))
    )
    (net (code "243") (name "unconnected-(U$1A-VBAT-Pad38)") (class "Default")
      (node (ref "U$1") (pin "38") (pinfunction "VBAT_38") (pintype "bidirectional"))
    )
    (net (code "244") (name "unconnected-(U$1A-~{RSTOUT}-Pad29)") (class "Default")
      (node (ref "U$1") (pin "29") (pinfunction "~{RSTOUT}_29") (pintype "bidirectional"))
    )
    (net (code "245") (name "unconnected-(U$1B-P0[2]{slash}U0_TXD{slash}U3_TXD-Pad202)") (class "Default")
      (node (ref "U$1") (pin "202") (pinfunction "P0[2]/U0_TXD/U3_TXD_202") (pintype "bidirectional"))
    )
    (net (code "246") (name "unconnected-(U$1B-P0[3]{slash}U0_RXD{slash}U3_RXD-Pad204)") (class "Default")
      (node (ref "U$1") (pin "204") (pinfunction "P0[3]/U0_RXD/U3_RXD_204") (pintype "bidirectional"))
    )
    (net (code "247") (name "unconnected-(U$1B-P0[12]{slash}~{USB_PPWR2}{slash}SSP1_MISO{slash}ADC0_IN[6]-Pad41)") (class "Default")
      (node (ref "U$1") (pin "41") (pinfunction "P0[12]/~{USB_PPWR2}/SSP1_MISO/ADC0_IN[6]_41") (pintype "bidirectional"))
    )
    (net (code "248") (name "unconnected-(U$1B-P0[21]{slash}U1_RI{slash}SD_PWR{slash}U4_OE{slash}CAN_RD1-Pad118)") (class "Default")
      (node (ref "U$1") (pin "118") (pinfunction "P0[21]/U1_RI/SD_PWR/U4_OE/CAN_RD1_118") (pintype "bidirectional"))
    )
    (net (code "249") (name "unconnected-(U$1B-P0[23]{slash}ADC0_IN[0]{slash}I2S_RX_SCK{slash}T3_CAP0-Pad18)") (class "Default")
      (node (ref "U$1") (pin "18") (pinfunction "P0[23]/ADC0_IN[0]/I2S_RX_SCK/T3_CAP0_18") (pintype "bidirectional"))
    )
    (net (code "250") (name "unconnected-(U$1B-P0[24]{slash}ADC0_IN[1]{slash}I2S_RX_WS{slash}T3_CAP1-Pad16)") (class "Default")
      (node (ref "U$1") (pin "16") (pinfunction "P0[24]/ADC0_IN[1]/I2S_RX_WS/T3_CAP1_16") (pintype "bidirectional"))
    )
    (net (code "251") (name "unconnected-(U$1B-P0[25]{slash}ADC0_IN[2]{slash}I2S_RX_SDA{slash}U3_TXD-Pad14)") (class "Default")
      (node (ref "U$1") (pin "14") (pinfunction "P0[25]/ADC0_IN[2]/I2S_RX_SDA/U3_TXD_14") (pintype "bidirectional"))
    )
    (net (code "252") (name "unconnected-(U$1B-P0[30]{slash}USB_D?1{slash}EINT_1-Pad62)") (class "Default")
      (node (ref "U$1") (pin "62") (pinfunction "P0[30]/USB_D?1/EINT_1_62") (pintype "bidirectional"))
    )
    (net (code "253") (name "unconnected-(U$1C-P1[3]{slash}ENET_TXD3{slash}SD_CMD{slash}PWM0_2-Pad177)") (class "Default")
      (node (ref "U$1") (pin "177") (pinfunction "P1[3]/ENET_TXD3/SD_CMD/PWM0_2_177") (pintype "bidirectional"))
    )
    (net (code "254") (name "unconnected-(U$1C-P1[5]{slash}ENET_TX_ER{slash}SD_PWR{slash}PWM0_3-Pad156)") (class "Default")
      (node (ref "U$1") (pin "156") (pinfunction "P1[5]/ENET_TX_ER/SD_PWR/PWM0_3_156") (pintype "bidirectional"))
    )
    (net (code "255") (name "unconnected-(U$1C-P1[6]{slash}ENET_TX_CLK{slash}SD_DAT[0]{slash}PWM0_4-Pad171)") (class "Default")
      (node (ref "U$1") (pin "171") (pinfunction "P1[6]/ENET_TX_CLK/SD_DAT[0]/PWM0_4_171") (pintype "bidirectional"))
    )
    (net (code "256") (name "unconnected-(U$1C-P1[9]{slash}ENET_RXD0{slash}T3_MAT0-Pad188)") (class "Default")
      (node (ref "U$1") (pin "188") (pinfunction "P1[9]/ENET_RXD0/T3_MAT0_188") (pintype "bidirectional"))
    )
    (net (code "257") (name "unconnected-(U$1C-P1[10]{slash}ENET_RXD1{slash}T3_CAP0-Pad186)") (class "Default")
      (node (ref "U$1") (pin "186") (pinfunction "P1[10]/ENET_RXD1/T3_CAP0_186") (pintype "bidirectional"))
    )
    (net (code "258") (name "unconnected-(U$1C-P1[13]{slash}ENET_RX_DV-Pad147)") (class "Default")
      (node (ref "U$1") (pin "147") (pinfunction "P1[13]/ENET_RX_DV_147") (pintype "bidirectional"))
    )
    (net (code "259") (name "unconnected-(U$1C-P1[14]{slash}ENET_RX_ER{slash}T2_CAP0-Pad184)") (class "Default")
      (node (ref "U$1") (pin "184") (pinfunction "P1[14]/ENET_RX_ER/T2_CAP0_184") (pintype "bidirectional"))
    )
    (net (code "260") (name "unconnected-(U$1C-P1[15]{slash}ENET_RX_CLK{slash}I2C2_SDA-Pad182)") (class "Default")
      (node (ref "U$1") (pin "182") (pinfunction "P1[15]/ENET_RX_CLK/I2C2_SDA_182") (pintype "bidirectional"))
    )
    (net (code "261") (name "unconnected-(U$1C-P1[16]{slash}ENET_MDC{slash}I2S_TX_MCLK-Pad180)") (class "Default")
      (node (ref "U$1") (pin "180") (pinfunction "P1[16]/ENET_MDC/I2S_TX_MCLK_180") (pintype "bidirectional"))
    )
    (net (code "262") (name "unconnected-(U$1C-P1[17]{slash}ENET_MDIO{slash}I2S_RX_MCLK-Pad178)") (class "Default")
      (node (ref "U$1") (pin "178") (pinfunction "P1[17]/ENET_MDIO/I2S_RX_MCLK_178") (pintype "bidirectional"))
    )
    (net (code "263") (name "unconnected-(U$1C-P1[18]{slash}USB_UP_LED1{slash}PWM1_1{slash}T1_CAP0{slash}SSP1_MISO-Pad66)") (class "Default")
      (node (ref "U$1") (pin "66") (pinfunction "P1[18]/USB_UP_LED1/PWM1_1/T1_CAP0/SSP1_MISO_66") (pintype "bidirectional"))
    )
    (net (code "264") (name "unconnected-(U$1C-P1[19]{slash}~{USB_TX_E1}{slash}~{USB_PPWR1}{slash}T1_CAP1{slash}MC_0A{slash}SSP1_SCK{slash}U2_OE-Pad68)") (class "Default")
      (node (ref "U$1") (pin "68") (pinfunction "P1[19]/~{USB_TX_E1}/~{USB_PPWR1}/T1_CAP1/MC_0A/SSP1_SCK/U2_OE_68") (pintype "bidirectional"))
    )
    (net (code "265") (name "unconnected-(U$1C-P1[30]{slash}USB_PWRD2{slash}USB_VBUS{slash}ADC0_IN[4]{slash}I2C0_SDA{slash}U3_OE-Pad42)") (class "Default")
      (node (ref "U$1") (pin "42") (pinfunction "P1[30]/USB_PWRD2/USB_VBUS/ADC0_IN[4]/I2C0_SDA/U3_OE_42") (pintype "bidirectional"))
    )
    (net (code "266") (name "unconnected-(U$1C-P1[31]{slash}USB_OVRCR2{slash}SSP1_SCK{slash}ADC0_IN[5]{slash}I2C0_SCL-Pad40)") (class "Default")
      (node (ref "U$1") (pin "40") (pinfunction "P1[31]/USB_OVRCR2/SSP1_SCK/ADC0_IN[5]/I2C0_SCL_40") (pintype "bidirectional"))
    )
    (net (code "267") (name "unconnected-(U$1D-P2[10]{slash}EINT_0{slash}NMI-Pad110)") (class "Default")
      (node (ref "U$1") (pin "110") (pinfunction "P2[10]/EINT_0/NMI_110") (pintype "bidirectional"))
    )
    (net (code "268") (name "unconnected-(U$1D-P2[11]{slash}EINT1{slash}SD_DAT[1]{slash}I2S_TX_SCK{slash}LCD_CLKIN-Pad108)") (class "Default")
      (node (ref "U$1") (pin "108") (pinfunction "P2[11]/EINT1/SD_DAT[1]/I2S_TX_SCK/LCD_CLKIN_108") (pintype "bidirectional"))
    )
    (net (code "269") (name "unconnected-(U$1D-P2[14]{slash}~{EMC_CS2}{slash}I2C1_SDA{slash}T2_CAP0-Pad91)") (class "Default")
      (node (ref "U$1") (pin "91") (pinfunction "P2[14]/~{EMC_CS2}/I2C1_SDA/T2_CAP0_91") (pintype "bidirectional"))
    )
    (net (code "270") (name "unconnected-(U$1D-P2[15{slash}~{EMC_CS3}{slash}I2C1_SCL{slash}T2_CAP1-Pad99)") (class "Default")
      (node (ref "U$1") (pin "99") (pinfunction "P2[15/~{EMC_CS3}/I2C1_SCL/T2_CAP1_99") (pintype "bidirectional"))
    )
    (net (code "271") (name "unconnected-(U$1D-P2[16]{slash}~{EMC_CAS}-Pad87)") (class "Default")
      (node (ref "U$1") (pin "87") (pinfunction "P2[16]/~{EMC_CAS}_87") (pintype "bidirectional"))
    )
    (net (code "272") (name "unconnected-(U$1D-P2[17]{slash}~{EMC_RAS}-Pad95)") (class "Default")
      (node (ref "U$1") (pin "95") (pinfunction "P2[17]/~{EMC_RAS}_95") (pintype "bidirectional"))
    )
    (net (code "273") (name "unconnected-(U$1D-P2[18]{slash}EMC_CLK[0]-Pad59)") (class "Default")
      (node (ref "U$1") (pin "59") (pinfunction "P2[18]/EMC_CLK[0]_59") (pintype "bidirectional"))
    )
    (net (code "274") (name "unconnected-(U$1D-P2[19]{slash}EMC_CLK[1]-Pad67)") (class "Default")
      (node (ref "U$1") (pin "67") (pinfunction "P2[19]/EMC_CLK[1]_67") (pintype "bidirectional"))
    )
    (net (code "275") (name "unconnected-(U$1D-P2[20]{slash}~{EMC_DYCS0}-Pad73)") (class "Default")
      (node (ref "U$1") (pin "73") (pinfunction "P2[20]/~{EMC_DYCS0}_73") (pintype "bidirectional"))
    )
    (net (code "276") (name "unconnected-(U$1D-P2[21]{slash}~{EMC_DYCS1}-Pad81)") (class "Default")
      (node (ref "U$1") (pin "81") (pinfunction "P2[21]/~{EMC_DYCS1}_81") (pintype "bidirectional"))
    )
    (net (code "277") (name "unconnected-(U$1D-P2[22]{slash}~{EMC_DYCS2}{slash}SSP0_SCK{slash}T3_CAP0-Pad85)") (class "Default")
      (node (ref "U$1") (pin "85") (pinfunction "P2[22]/~{EMC_DYCS2}/SSP0_SCK/T3_CAP0_85") (pintype "bidirectional"))
    )
    (net (code "278") (name "unconnected-(U$1D-P2[23]{slash}~{EMC_DYCS3}{slash}SSP0_SSEL{slash}T3_CAP1-Pad64)") (class "Default")
      (node (ref "U$1") (pin "64") (pinfunction "P2[23]/~{EMC_DYCS3}/SSP0_SSEL/T3_CAP1_64") (pintype "bidirectional"))
    )
    (net (code "279") (name "unconnected-(U$1D-P2[24]{slash}EMC_CKE0-Pad53)") (class "Default")
      (node (ref "U$1") (pin "53") (pinfunction "P2[24]/EMC_CKE0_53") (pintype "bidirectional"))
    )
    (net (code "280") (name "unconnected-(U$1D-P2[25]{slash}EMC_CKE1-Pad54)") (class "Default")
      (node (ref "U$1") (pin "54") (pinfunction "P2[25]/EMC_CKE1_54") (pintype "bidirectional"))
    )
    (net (code "281") (name "unconnected-(U$1D-P2[26]{slash}EMC_CKE2{slash}SSP0_MISO{slash}T3_MAT0-Pad57)") (class "Default")
      (node (ref "U$1") (pin "57") (pinfunction "P2[26]/EMC_CKE2/SSP0_MISO/T3_MAT0_57") (pintype "bidirectional"))
    )
    (net (code "282") (name "unconnected-(U$1D-P2[27]{slash}EMC_CKE3{slash}SSP0_MOSI{slash}T3_MAT1-Pad47)") (class "Default")
      (node (ref "U$1") (pin "47") (pinfunction "P2[27]/EMC_CKE3/SSP0_MOSI/T3_MAT1_47") (pintype "bidirectional"))
    )
    (net (code "283") (name "unconnected-(U$1D-P2[28]{slash}EMC_DQM0-Pad49)") (class "Default")
      (node (ref "U$1") (pin "49") (pinfunction "P2[28]/EMC_DQM0_49") (pintype "bidirectional"))
    )
    (net (code "284") (name "unconnected-(U$1D-P2[29]{slash}EMC_DQM1-Pad43)") (class "Default")
      (node (ref "U$1") (pin "43") (pinfunction "P2[29]/EMC_DQM1_43") (pintype "bidirectional"))
    )
    (net (code "285") (name "unconnected-(U$1D-P2[30]{slash}EMC_DQM2{slash}I2C2_SDA{slash}T3_MAT2-Pad31)") (class "Default")
      (node (ref "U$1") (pin "31") (pinfunction "P2[30]/EMC_DQM2/I2C2_SDA/T3_MAT2_31") (pintype "bidirectional"))
    )
    (net (code "286") (name "unconnected-(U$1D-P2[31]{slash}EMC_DQM3{slash}I2C2_SCL{slash}T3_MAT3-Pad39)") (class "Default")
      (node (ref "U$1") (pin "39") (pinfunction "P2[31]/EMC_DQM3/I2C2_SCL/T3_MAT3_39") (pintype "bidirectional"))
    )
    (net (code "287") (name "unconnected-(U$1E-P3[16]{slash}EMC_D[16]{slash}PWM0_1{slash}U1_TXD-Pad137)") (class "Default")
      (node (ref "U$1") (pin "137") (pinfunction "P3[16]/EMC_D[16]/PWM0_1/U1_TXD_137") (pintype "bidirectional"))
    )
    (net (code "288") (name "unconnected-(U$1E-P3[17]{slash}EMC_D[17]{slash}PWM0_2{slash}U1_RXD-Pad143)") (class "Default")
      (node (ref "U$1") (pin "143") (pinfunction "P3[17]/EMC_D[17]/PWM0_2/U1_RXD_143") (pintype "bidirectional"))
    )
    (net (code "289") (name "unconnected-(U$1E-P3[18]{slash}EMC_D[18]{slash}PWM0_3{slash}U1_CTS-Pad151)") (class "Default")
      (node (ref "U$1") (pin "151") (pinfunction "P3[18]/EMC_D[18]/PWM0_3/U1_CTS_151") (pintype "bidirectional"))
    )
    (net (code "290") (name "unconnected-(U$1E-P3[19]{slash}EMC_D[19]{slash}PWM0_4{slash}U1_DCD-Pad161)") (class "Default")
      (node (ref "U$1") (pin "161") (pinfunction "P3[19]/EMC_D[19]/PWM0_4/U1_DCD_161") (pintype "bidirectional"))
    )
    (net (code "291") (name "unconnected-(U$1E-P3[20]{slash}EMC_D[20]{slash}PWM0_5{slash}U1_DSR-Pad167)") (class "Default")
      (node (ref "U$1") (pin "167") (pinfunction "P3[20]/EMC_D[20]/PWM0_5/U1_DSR_167") (pintype "bidirectional"))
    )
    (net (code "292") (name "unconnected-(U$1E-P3[21]{slash}EMC_D[21]{slash}PWM0_6{slash}U1_DTR-Pad175)") (class "Default")
      (node (ref "U$1") (pin "175") (pinfunction "P3[21]/EMC_D[21]/PWM0_6/U1_DTR_175") (pintype "bidirectional"))
    )
    (net (code "293") (name "unconnected-(U$1E-P3[22]{slash}EMC_D[22]{slash}PWM0_CAP0{slash}U1_RI-Pad195)") (class "Default")
      (node (ref "U$1") (pin "195") (pinfunction "P3[22]/EMC_D[22]/PWM0_CAP0/U1_RI_195") (pintype "bidirectional"))
    )
    (net (code "294") (name "unconnected-(U$1E-P3[23]{slash}EMC_D[23]{slash}PWM1_CAP0{slash}T0_CAP0-Pad65)") (class "Default")
      (node (ref "U$1") (pin "65") (pinfunction "P3[23]/EMC_D[23]/PWM1_CAP0/T0_CAP0_65") (pintype "bidirectional"))
    )
    (net (code "295") (name "unconnected-(U$1E-P3[24]{slash}EMC_D[24]{slash}PWM1[1]{slash}T0_CAP1-Pad58)") (class "Default")
      (node (ref "U$1") (pin "58") (pinfunction "P3[24]/EMC_D[24]/PWM1[1]/T0_CAP1_58") (pintype "bidirectional"))
    )
    (net (code "296") (name "unconnected-(U$1E-P3[25]{slash}EMC_D[25]{slash}PWM1[2]{slash}T0_MAT0-Pad56)") (class "Default")
      (node (ref "U$1") (pin "56") (pinfunction "P3[25]/EMC_D[25]/PWM1[2]/T0_MAT0_56") (pintype "bidirectional"))
    )
    (net (code "297") (name "unconnected-(U$1E-P3[26]{slash}EMC_D[26]{slash}PWM1[3]{slash}T0_MAT1{slash}STCLK-Pad55)") (class "Default")
      (node (ref "U$1") (pin "55") (pinfunction "P3[26]/EMC_D[26]/PWM1[3]/T0_MAT1/STCLK_55") (pintype "bidirectional"))
    )
    (net (code "298") (name "unconnected-(U$1E-P3[27]{slash}EMC_D[27]{slash}PWM1[4]{slash}T1_CAP0-Pad203)") (class "Default")
      (node (ref "U$1") (pin "203") (pinfunction "P3[27]/EMC_D[27]/PWM1[4]/T1_CAP0_203") (pintype "bidirectional"))
    )
    (net (code "299") (name "unconnected-(U$1E-P3[28]{slash}EMC_D[28]{slash}PWM1[5]{slash}T1_CAP1-Pad5)") (class "Default")
      (node (ref "U$1") (pin "5") (pinfunction "P3[28]/EMC_D[28]/PWM1[5]/T1_CAP1_5") (pintype "bidirectional"))
    )
    (net (code "300") (name "unconnected-(U$1E-P3[29]{slash}EMC_D[29]{slash}PWM1[6]{slash}T1_MAT0-Pad11)") (class "Default")
      (node (ref "U$1") (pin "11") (pinfunction "P3[29]/EMC_D[29]/PWM1[6]/T1_MAT0_11") (pintype "bidirectional"))
    )
    (net (code "301") (name "unconnected-(U$1E-P3[30]{slash}EMC_D[30]{slash}U1_RTS{slash}T1_MAT1-Pad19)") (class "Default")
      (node (ref "U$1") (pin "19") (pinfunction "P3[30]/EMC_D[30]/U1_RTS/T1_MAT1_19") (pintype "bidirectional"))
    )
    (net (code "302") (name "unconnected-(U$1E-P3[31]{slash}EMC_D[31]{slash}T1_MAT2-Pad25)") (class "Default")
      (node (ref "U$1") (pin "25") (pinfunction "P3[31]/EMC_D[31]/T1_MAT2_25") (pintype "bidirectional"))
    )
    (net (code "303") (name "unconnected-(U$1F-P4[20]{slash}EMC_A[20]{slash}I2C2_SDA{slash}SSP1_SCK-Pad109)") (class "Default")
      (node (ref "U$1") (pin "109") (pinfunction "P4[20]/EMC_A[20]/I2C2_SDA/SSP1_SCK_109") (pintype "bidirectional"))
    )
    (net (code "304") (name "unconnected-(U$1F-P4[21]{slash}EMC_A[21]{slash}I2C2_SCL{slash}SSP1_SSEL-Pad115)") (class "Default")
      (node (ref "U$1") (pin "115") (pinfunction "P4[21]/EMC_A[21]/I2C2_SCL/SSP1_SSEL_115") (pintype "bidirectional"))
    )
    (net (code "305") (name "unconnected-(U$1F-P4[22]{slash}EMC_A[22]{slash}U2_TXD{slash}SSP1_MISO-Pad123)") (class "Default")
      (node (ref "U$1") (pin "123") (pinfunction "P4[22]/EMC_A[22]/U2_TXD/SSP1_MISO_123") (pintype "bidirectional"))
    )
    (net (code "306") (name "unconnected-(U$1F-P4[23]{slash}EMC_A[23]{slash}U2_RXD{slash}SSP1_MOSI-Pad129)") (class "Default")
      (node (ref "U$1") (pin "129") (pinfunction "P4[23]/EMC_A[23]/U2_RXD/SSP1_MOSI_129") (pintype "bidirectional"))
    )
    (net (code "307") (name "unconnected-(U$2-SCL-PadP$10)") (class "Default")
      (node (ref "U$2") (pin "P$10") (pinfunction "SCL_P$10") (pintype "bidirectional"))
    )
    (net (code "308") (name "unconnected-(U$2-SDA-PadP$11)") (class "Default")
      (node (ref "U$2") (pin "P$11") (pinfunction "SDA_P$11") (pintype "bidirectional"))
    )
    (net (code "309") (name "unconnected-(U$2-~{CS}-PadP$9)") (class "Default")
      (node (ref "U$2") (pin "P$9") (pinfunction "~{CS}_P$9") (pintype "bidirectional"))
    )
    (net (code "310") (name "unconnected-(U$2-~{RST}-PadP$8)") (class "Default")
      (node (ref "U$2") (pin "P$8") (pinfunction "~{RST}_P$8") (pintype "bidirectional"))
    )
    (net (code "311") (name "unconnected-(U$4-PadP$3)") (class "Default")
      (node (ref "U$4") (pin "P$3") (pinfunction "P$3_P$3") (pintype "no_connect"))
    )
    (net (code "312") (name "unconnected-(U$4-PadP$4)") (class "Default")
      (node (ref "U$4") (pin "P$4") (pinfunction "P$4_P$4") (pintype "no_connect"))
    )
    (net (code "313") (name "{slash}RESET") (class "Default")
      (node (ref "C16") (pin "1") (pinfunction "1_1") (pintype "passive"))
      (node (ref "J6") (pin "P$10") (pinfunction "S10_P$10") (pintype "passive"))
      (node (ref "J7") (pin "6") (pinfunction "S6_6") (pintype "passive"))
      (node (ref "R11") (pin "1") (pinfunction "1_1") (pintype "passive"))
      (node (ref "SW1") (pin "P$1") (pinfunction "P1_P$1") (pintype "passive"))
      (node (ref "SW1") (pin "P$2") (pinfunction "P_P$2") (pintype "passive"))
      (node (ref "U$1") (pin "35") (pinfunction "~{RESET}_35") (pintype "bidirectional"))
    )
    (net (code "314") (name "~{BLS0}") (class "Default")
      (node (ref "U$1") (pin "119") (pinfunction "P4[26]/~{EMC_BLS0}_119") (pintype "bidirectional"))
      (node (ref "U4") (pin "15") (pinfunction "~{BLE}_15") (pintype "input"))
    )
    (net (code "315") (name "~{BLS1}") (class "Default")
      (node (ref "U$1") (pin "139") (pinfunction "P4[27]/~{EMC_BLS1}_139") (pintype "bidirectional"))
      (node (ref "U4") (pin "14") (pinfunction "~{BHE}_14") (pintype "input"))
    )
    (net (code "316") (name "~{CS0}") (class "Default")
      (node (ref "U$1") (pin "187") (pinfunction "P4[30]/~{EMC_CS0}_187") (pintype "bidirectional"))
      (node (ref "U4") (pin "26") (pinfunction "~{CE}_26") (pintype "input"))
    )
    (net (code "317") (name "~{CS1}") (class "Default")
      (node (ref "U$1") (pin "193") (pinfunction "P4[31]/~{EMC_CS1}_193") (pintype "bidirectional"))
    )
    (net (code "318") (name "~{OE}") (class "Default")
      (node (ref "U$1") (pin "183") (pinfunction "P4[24]/~{EMC_OE}_183") (pintype "bidirectional"))
      (node (ref "U4") (pin "28") (pinfunction "~{OE}_28") (pintype "input"))
    )
    (net (code "319") (name "~{WE}") (class "Default")
      (node (ref "U$1") (pin "179") (pinfunction "P4[25]/~{EMC_WE}_179") (pintype "bidirectional"))
      (node (ref "U4") (pin "11") (pinfunction "~{WE}_11") (pintype "input"))
    )
  )
)
